# Sheet1.net
KiCad netlist of a schematic drawn in Altium Designer
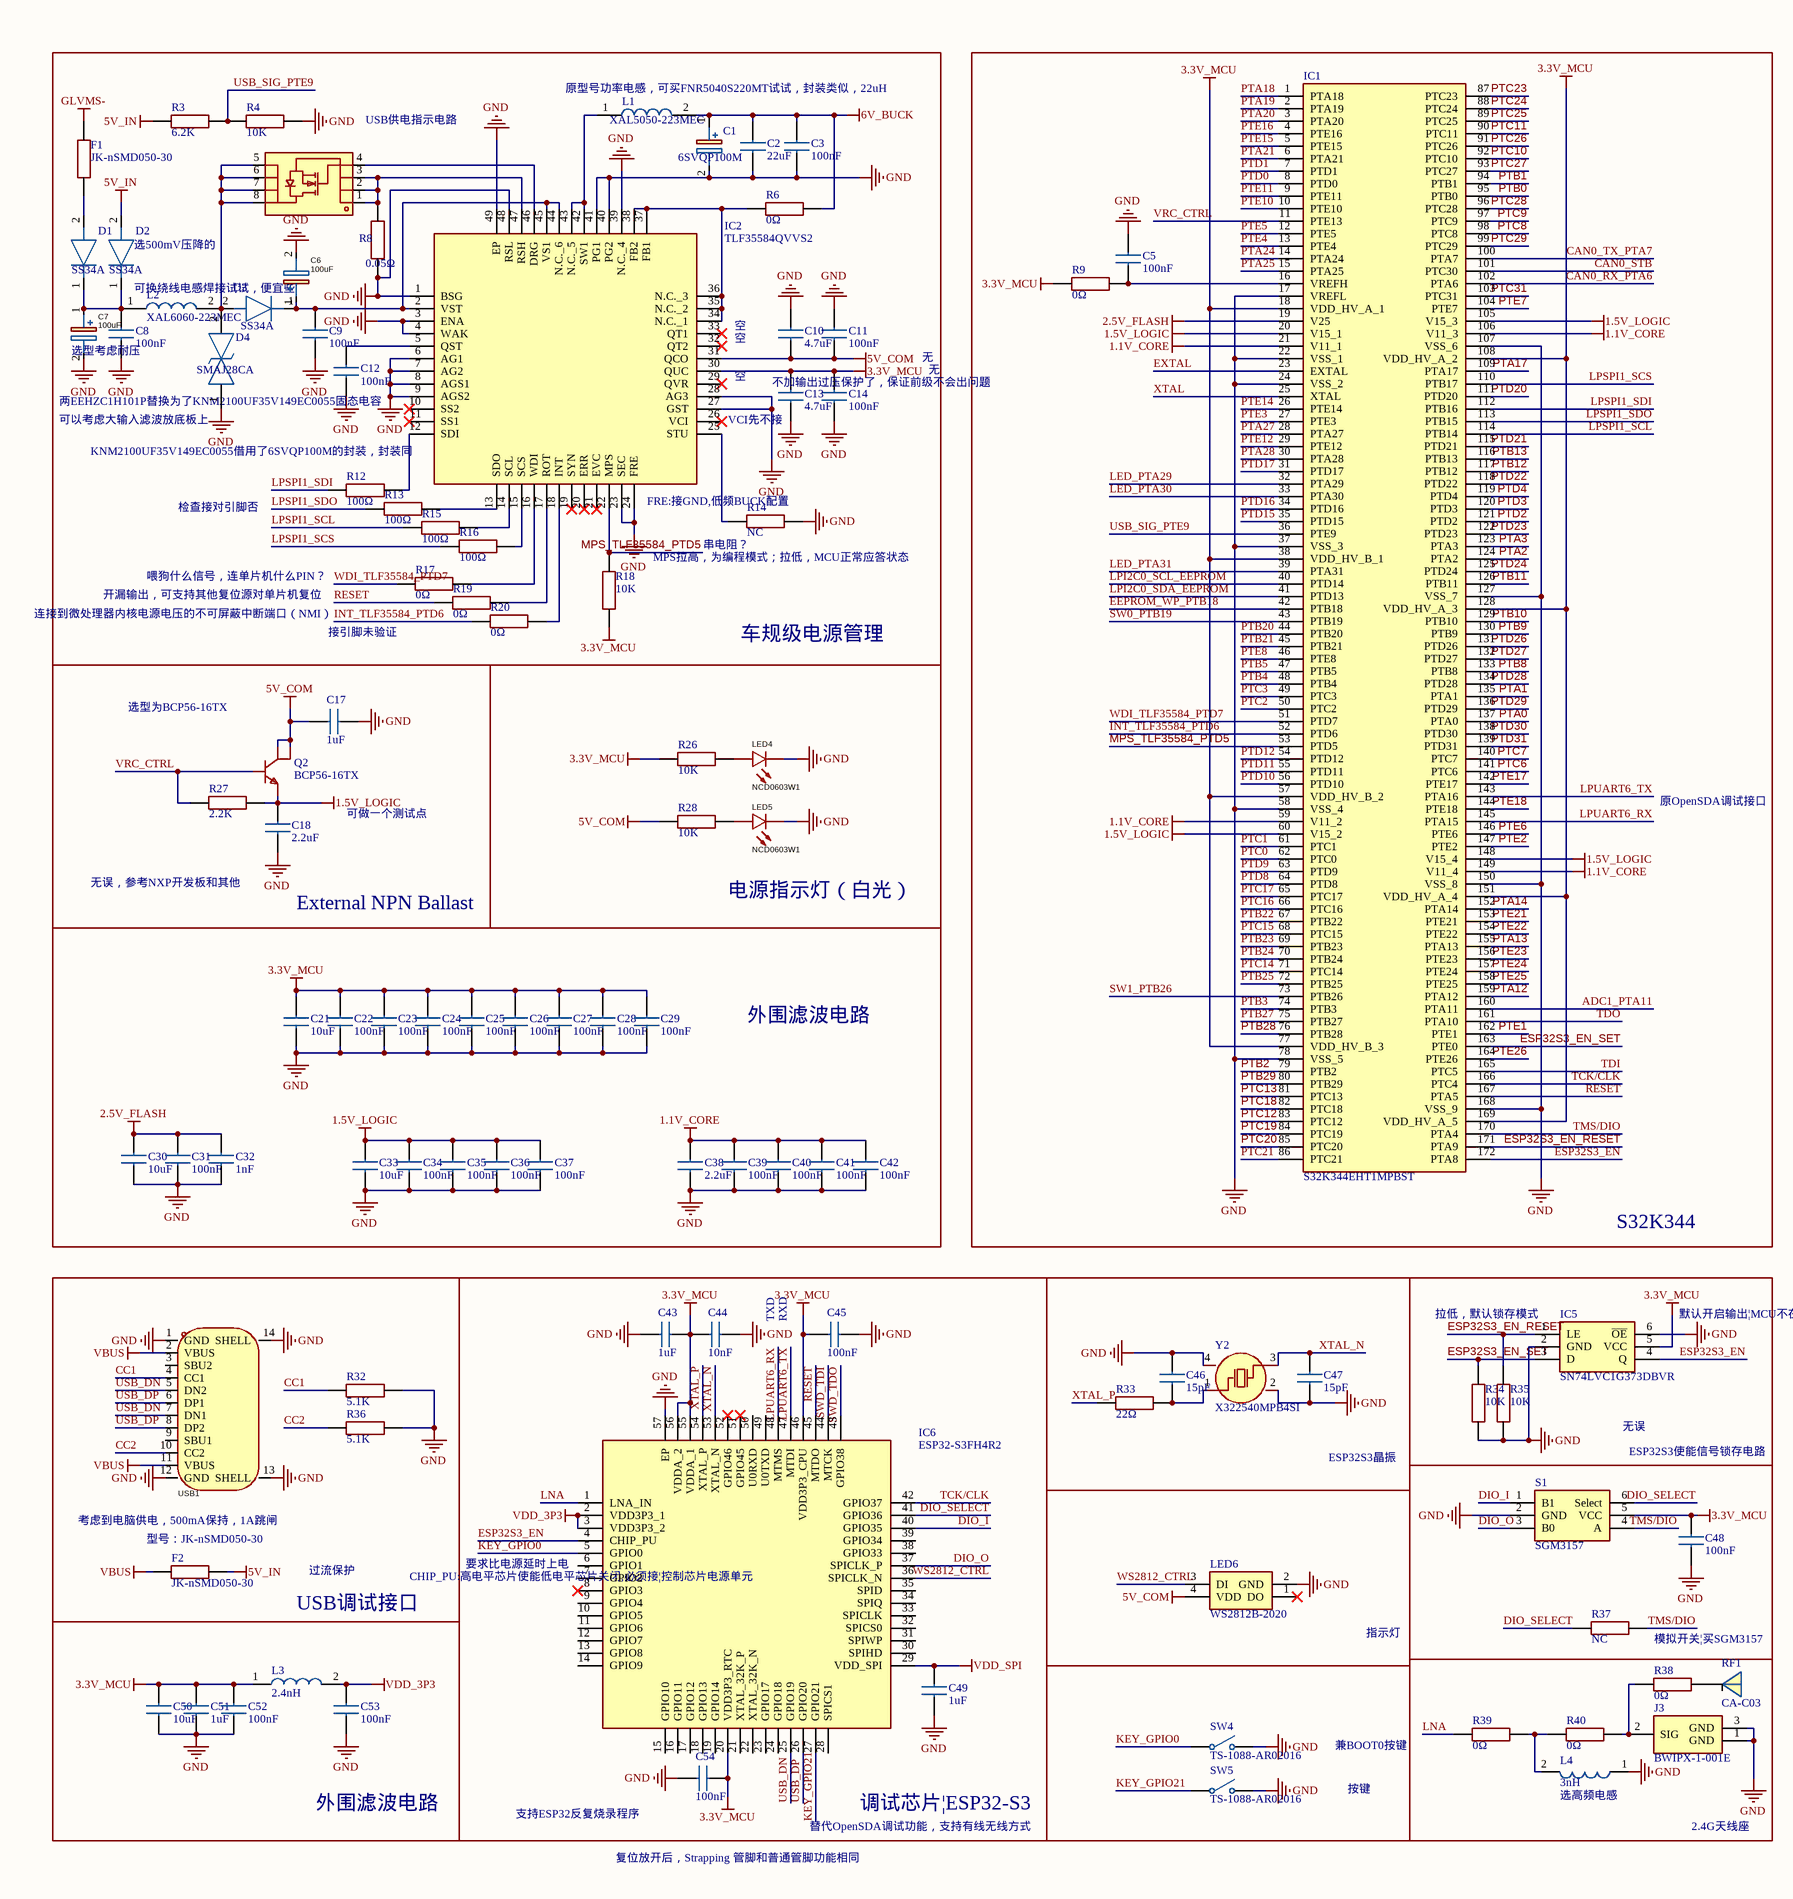
[diagram p0: Sheet1.SchDoc, left]
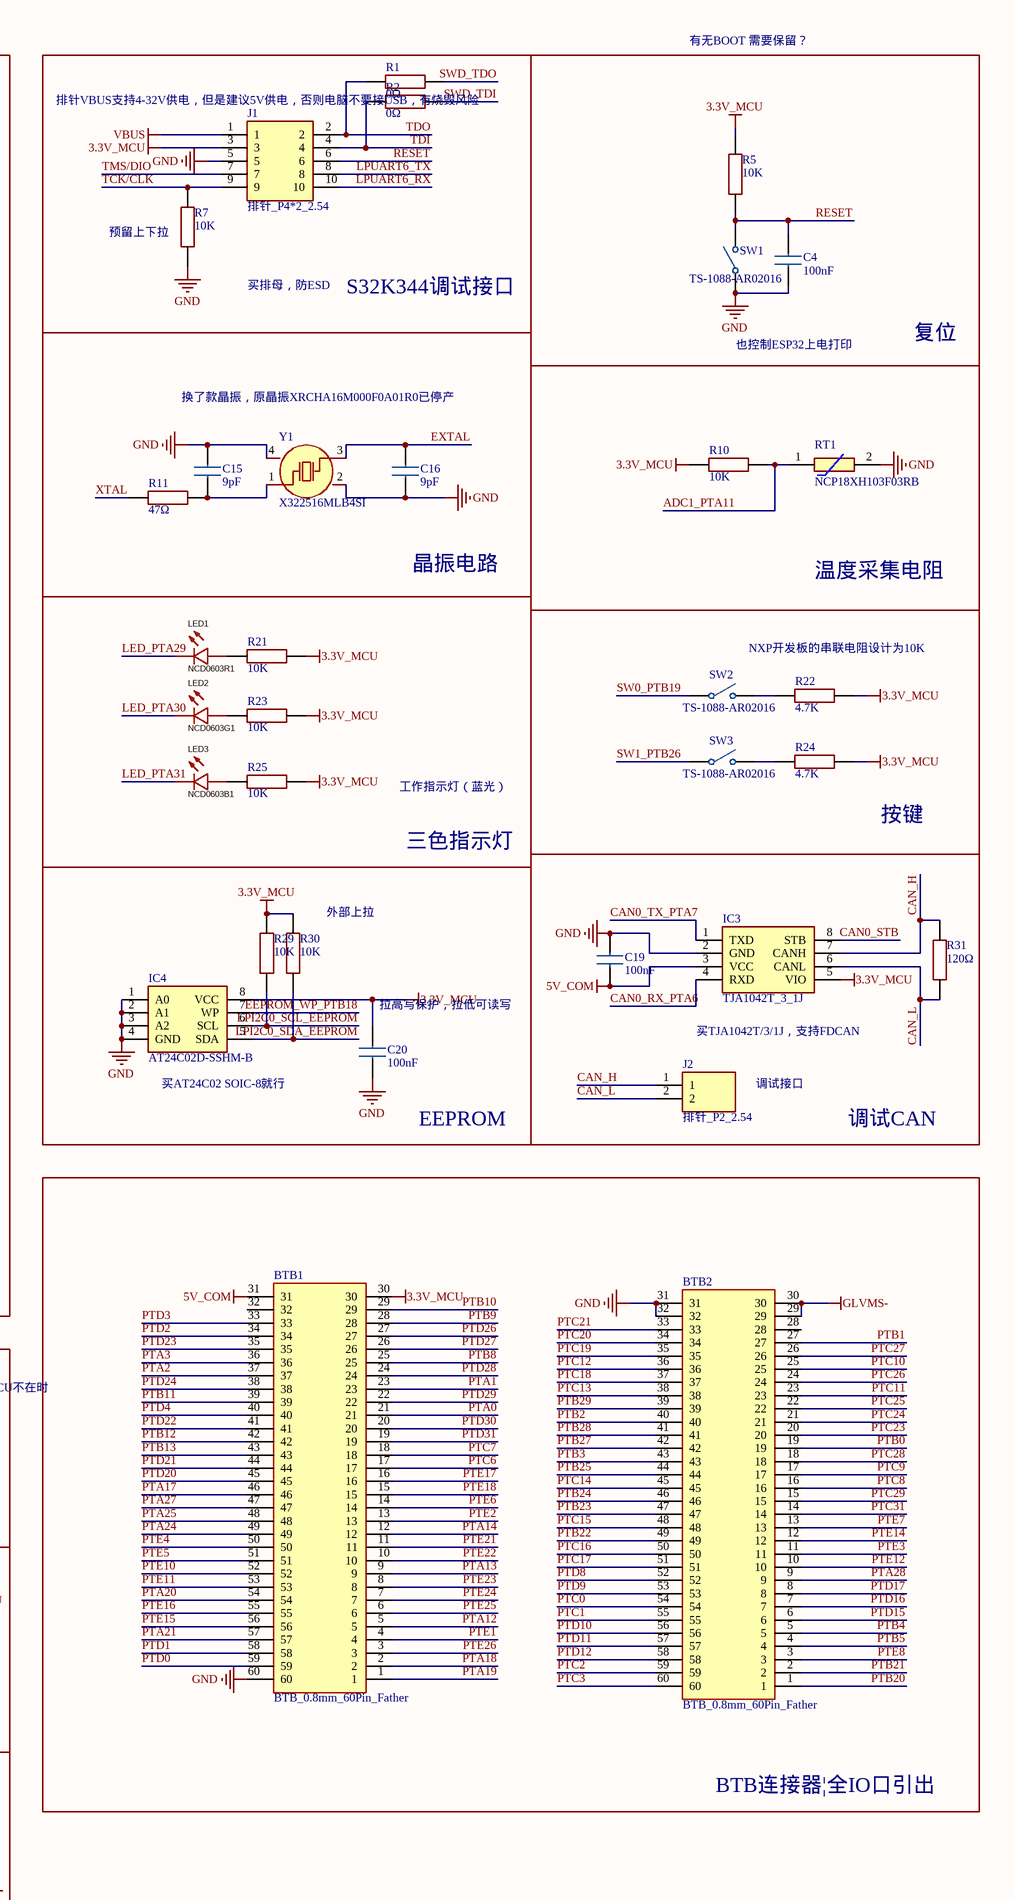
[diagram p1: Sheet1.SchDoc, right]

(export (version "E")
  (design (tool "Eeschema 10.0.6"))
  (components
    (comp (ref "BTB1")
      (value "BTB_0.8mm_60Pin_Father")
      (footprint "BTB_0.8mm_60PIN_F")
      (libsource (lib "Connector") (part "BTB_0.8mm_60Pin_Father"))
    )
    (comp (ref "BTB2")
      (value "BTB_0.8mm_60Pin_Father")
      (footprint "BTB_0.8mm_60PIN_F")
      (libsource (lib "Connector") (part "BTB_0.8mm_60Pin_Father"))
    )
    (comp (ref "C1")
      (value "6SVQP100M")
      (footprint "16SVF180M")
      (description "Capacitor Polarised")
      (fields (field (name "MOUSER PART NUMBER") "667-6SVQP100M"))
      (libsource (lib "Resistor^Capacitor^Inductor") (part "6SVQP100M"))
    )
    (comp (ref "C2")
      (value "22uF")
      (footprint "CAPC1608X90N")
      (description "Capacitor CC0603KRX7R9BB104")
      (fields
        (field (name "MANUFACTURER_PART_NUMBER") "CC0603KRX7R9BB104")
        (field (name "MOUSER PART NUMBER") "603-CC603KRX7R9BB104")
      )
      (libsource (lib "Resistor^Capacitor^Inductor") (part "C0603"))
    )
    (comp (ref "C3")
      (value "100nF")
      (footprint "CAPC1608X90N")
      (description "Capacitor CC0603KRX7R9BB104")
      (fields
        (field (name "MANUFACTURER_PART_NUMBER") "CC0603KRX7R9BB104")
        (field (name "MOUSER PART NUMBER") "603-CC603KRX7R9BB104")
      )
      (libsource (lib "Resistor^Capacitor^Inductor") (part "C0603"))
    )
    (comp (ref "C4")
      (value "100nF")
      (footprint "CAPC1608X90N")
      (description "Capacitor CC0603KRX7R9BB104")
      (fields
        (field (name "MANUFACTURER_PART_NUMBER") "CC0603KRX7R9BB104")
        (field (name "MOUSER PART NUMBER") "603-CC603KRX7R9BB104")
      )
      (libsource (lib "Resistor^Capacitor^Inductor") (part "C0603"))
    )
    (comp (ref "C5")
      (value "100nF")
      (footprint "CAPC1608X90N")
      (description "Capacitor CC0603KRX7R9BB104")
      (fields
        (field (name "MANUFACTURER_PART_NUMBER") "CC0603KRX7R9BB104")
        (field (name "MOUSER PART NUMBER") "603-CC603KRX7R9BB104")
      )
      (libsource (lib "Resistor^Capacitor^Inductor") (part "C0603"))
    )
    (comp (ref "C6")
      (value "100uF")
      (footprint "16SVF180M")
      (fields
        (field (name "MANUFACTURER") "KNSCHA(科尼盛)")
        (field (name "MANUFACTURER PART") "KNM2100UF35V149EC0055")
        (field (name "TOLERANCE") "±20%")
      )
      (libsource (lib "Resistor^Capacitor^Inductor") (part "KNM2100UF35V149EC0055"))
    )
    (comp (ref "C7")
      (value "100uF")
      (footprint "16SVF180M")
      (fields
        (field (name "MANUFACTURER") "KNSCHA(科尼盛)")
        (field (name "MANUFACTURER PART") "KNM2100UF35V149EC0055")
        (field (name "TOLERANCE") "±20%")
      )
      (libsource (lib "") (part "KNM2100UF35V149EC0055_1"))
    )
    (comp (ref "C8")
      (value "100nF")
      (footprint "CAPC1608X90N")
      (description "Capacitor CC0603KRX7R9BB104")
      (fields
        (field (name "MANUFACTURER_PART_NUMBER") "CC0603KRX7R9BB104")
        (field (name "MOUSER PART NUMBER") "603-CC603KRX7R9BB104")
      )
      (libsource (lib "Resistor^Capacitor^Inductor") (part "C0603"))
    )
    (comp (ref "C9")
      (value "100nF")
      (footprint "CAPC1608X90N")
      (description "Capacitor CC0603KRX7R9BB104")
      (fields
        (field (name "MANUFACTURER_PART_NUMBER") "CC0603KRX7R9BB104")
        (field (name "MOUSER PART NUMBER") "603-CC603KRX7R9BB104")
      )
      (libsource (lib "Resistor^Capacitor^Inductor") (part "C0603"))
    )
    (comp (ref "C10")
      (value "4.7uF")
      (footprint "CAPC1608X90N")
      (description "Capacitor CC0603KRX7R9BB104")
      (fields
        (field (name "MANUFACTURER_PART_NUMBER") "CC0603KRX7R9BB104")
        (field (name "MOUSER PART NUMBER") "603-CC603KRX7R9BB104")
      )
      (libsource (lib "Resistor^Capacitor^Inductor") (part "C0603"))
    )
    (comp (ref "C11")
      (value "100nF")
      (footprint "CAPC1608X90N")
      (description "Capacitor CC0603KRX7R9BB104")
      (fields
        (field (name "MANUFACTURER_PART_NUMBER") "CC0603KRX7R9BB104")
        (field (name "MOUSER PART NUMBER") "603-CC603KRX7R9BB104")
      )
      (libsource (lib "Resistor^Capacitor^Inductor") (part "C0603"))
    )
    (comp (ref "C12")
      (value "100nF")
      (footprint "CAPC1608X90N")
      (description "Capacitor CC0603KRX7R9BB104")
      (fields
        (field (name "MANUFACTURER_PART_NUMBER") "CC0603KRX7R9BB104")
        (field (name "MOUSER PART NUMBER") "603-CC603KRX7R9BB104")
      )
      (libsource (lib "Resistor^Capacitor^Inductor") (part "C0603"))
    )
    (comp (ref "C13")
      (value "4.7uF")
      (footprint "CAPC1608X90N")
      (description "Capacitor CC0603KRX7R9BB104")
      (fields
        (field (name "MANUFACTURER_PART_NUMBER") "CC0603KRX7R9BB104")
        (field (name "MOUSER PART NUMBER") "603-CC603KRX7R9BB104")
      )
      (libsource (lib "Resistor^Capacitor^Inductor") (part "C0603"))
    )
    (comp (ref "C14")
      (value "100nF")
      (footprint "CAPC1608X90N")
      (description "Capacitor CC0603KRX7R9BB104")
      (fields
        (field (name "MANUFACTURER_PART_NUMBER") "CC0603KRX7R9BB104")
        (field (name "MOUSER PART NUMBER") "603-CC603KRX7R9BB104")
      )
      (libsource (lib "Resistor^Capacitor^Inductor") (part "C0603"))
    )
    (comp (ref "C15")
      (value "9pF")
      (footprint "CAPC1608X90N")
      (description "Capacitor CC0603KRX7R9BB104")
      (fields
        (field (name "MANUFACTURER_PART_NUMBER") "CC0603KRX7R9BB104")
        (field (name "MOUSER PART NUMBER") "603-CC603KRX7R9BB104")
      )
      (libsource (lib "Resistor^Capacitor^Inductor") (part "C0603"))
    )
    (comp (ref "C16")
      (value "9pF")
      (footprint "CAPC1608X90N")
      (description "Capacitor CC0603KRX7R9BB104")
      (fields
        (field (name "MANUFACTURER_PART_NUMBER") "CC0603KRX7R9BB104")
        (field (name "MOUSER PART NUMBER") "603-CC603KRX7R9BB104")
      )
      (libsource (lib "Resistor^Capacitor^Inductor") (part "C0603"))
    )
    (comp (ref "C17")
      (value "1uF")
      (footprint "CAPC1608X90N")
      (description "Capacitor CC0603KRX7R9BB104")
      (fields
        (field (name "MANUFACTURER_PART_NUMBER") "CC0603KRX7R9BB104")
        (field (name "MOUSER PART NUMBER") "603-CC603KRX7R9BB104")
      )
      (libsource (lib "Resistor^Capacitor^Inductor") (part "C0603"))
    )
    (comp (ref "C18")
      (value "2.2uF")
      (footprint "CAPC1608X90N")
      (description "Capacitor CC0603KRX7R9BB104")
      (fields
        (field (name "MANUFACTURER_PART_NUMBER") "CC0603KRX7R9BB104")
        (field (name "MOUSER PART NUMBER") "603-CC603KRX7R9BB104")
      )
      (libsource (lib "Resistor^Capacitor^Inductor") (part "C0603"))
    )
    (comp (ref "C19")
      (value "100nF")
      (footprint "CAPC1608X90N")
      (description "Capacitor CC0603KRX7R9BB104")
      (fields
        (field (name "MANUFACTURER_PART_NUMBER") "CC0603KRX7R9BB104")
        (field (name "MOUSER PART NUMBER") "603-CC603KRX7R9BB104")
      )
      (libsource (lib "Resistor^Capacitor^Inductor") (part "C0603"))
    )
    (comp (ref "C20")
      (value "100nF")
      (footprint "CAPC1608X90N")
      (description "Capacitor CC0603KRX7R9BB104")
      (fields
        (field (name "MANUFACTURER_PART_NUMBER") "CC0603KRX7R9BB104")
        (field (name "MOUSER PART NUMBER") "603-CC603KRX7R9BB104")
      )
      (libsource (lib "Resistor^Capacitor^Inductor") (part "C0603"))
    )
    (comp (ref "C21")
      (value "10uF")
      (footprint "CAPC1608X90N")
      (description "Capacitor CC0603KRX7R9BB104")
      (fields
        (field (name "MANUFACTURER_PART_NUMBER") "CC0603KRX7R9BB104")
        (field (name "MOUSER PART NUMBER") "603-CC603KRX7R9BB104")
      )
      (libsource (lib "Resistor^Capacitor^Inductor") (part "C0603"))
    )
    (comp (ref "C22")
      (value "100nF")
      (footprint "CAPC1608X90N")
      (description "Capacitor CC0603KRX7R9BB104")
      (fields
        (field (name "MANUFACTURER_PART_NUMBER") "CC0603KRX7R9BB104")
        (field (name "MOUSER PART NUMBER") "603-CC603KRX7R9BB104")
      )
      (libsource (lib "Resistor^Capacitor^Inductor") (part "C0603"))
    )
    (comp (ref "C23")
      (value "100nF")
      (footprint "CAPC1608X90N")
      (description "Capacitor CC0603KRX7R9BB104")
      (fields
        (field (name "MANUFACTURER_PART_NUMBER") "CC0603KRX7R9BB104")
        (field (name "MOUSER PART NUMBER") "603-CC603KRX7R9BB104")
      )
      (libsource (lib "Resistor^Capacitor^Inductor") (part "C0603"))
    )
    (comp (ref "C24")
      (value "100nF")
      (footprint "CAPC1608X90N")
      (description "Capacitor CC0603KRX7R9BB104")
      (fields
        (field (name "MANUFACTURER_PART_NUMBER") "CC0603KRX7R9BB104")
        (field (name "MOUSER PART NUMBER") "603-CC603KRX7R9BB104")
      )
      (libsource (lib "Resistor^Capacitor^Inductor") (part "C0603"))
    )
    (comp (ref "C25")
      (value "100nF")
      (footprint "CAPC1608X90N")
      (description "Capacitor CC0603KRX7R9BB104")
      (fields
        (field (name "MANUFACTURER_PART_NUMBER") "CC0603KRX7R9BB104")
        (field (name "MOUSER PART NUMBER") "603-CC603KRX7R9BB104")
      )
      (libsource (lib "Resistor^Capacitor^Inductor") (part "C0603"))
    )
    (comp (ref "C26")
      (value "100nF")
      (footprint "CAPC1608X90N")
      (description "Capacitor CC0603KRX7R9BB104")
      (fields
        (field (name "MANUFACTURER_PART_NUMBER") "CC0603KRX7R9BB104")
        (field (name "MOUSER PART NUMBER") "603-CC603KRX7R9BB104")
      )
      (libsource (lib "Resistor^Capacitor^Inductor") (part "C0603"))
    )
    (comp (ref "C27")
      (value "100nF")
      (footprint "CAPC1608X90N")
      (description "Capacitor CC0603KRX7R9BB104")
      (fields
        (field (name "MANUFACTURER_PART_NUMBER") "CC0603KRX7R9BB104")
        (field (name "MOUSER PART NUMBER") "603-CC603KRX7R9BB104")
      )
      (libsource (lib "Resistor^Capacitor^Inductor") (part "C0603"))
    )
    (comp (ref "C28")
      (value "100nF")
      (footprint "CAPC1608X90N")
      (description "Capacitor CC0603KRX7R9BB104")
      (fields
        (field (name "MANUFACTURER_PART_NUMBER") "CC0603KRX7R9BB104")
        (field (name "MOUSER PART NUMBER") "603-CC603KRX7R9BB104")
      )
      (libsource (lib "Resistor^Capacitor^Inductor") (part "C0603"))
    )
    (comp (ref "C29")
      (value "100nF")
      (footprint "CAPC1608X90N")
      (description "Capacitor CC0603KRX7R9BB104")
      (fields
        (field (name "MANUFACTURER_PART_NUMBER") "CC0603KRX7R9BB104")
        (field (name "MOUSER PART NUMBER") "603-CC603KRX7R9BB104")
      )
      (libsource (lib "Resistor^Capacitor^Inductor") (part "C0603"))
    )
    (comp (ref "C30")
      (value "10uF")
      (footprint "CAPC1608X90N")
      (description "Capacitor CC0603KRX7R9BB104")
      (fields
        (field (name "MANUFACTURER_PART_NUMBER") "CC0603KRX7R9BB104")
        (field (name "MOUSER PART NUMBER") "603-CC603KRX7R9BB104")
      )
      (libsource (lib "Resistor^Capacitor^Inductor") (part "C0603"))
    )
    (comp (ref "C31")
      (value "100nF")
      (footprint "CAPC1608X90N")
      (description "Capacitor CC0603KRX7R9BB104")
      (fields
        (field (name "MANUFACTURER_PART_NUMBER") "CC0603KRX7R9BB104")
        (field (name "MOUSER PART NUMBER") "603-CC603KRX7R9BB104")
      )
      (libsource (lib "Resistor^Capacitor^Inductor") (part "C0603"))
    )
    (comp (ref "C32")
      (value "1nF")
      (footprint "CAPC1608X90N")
      (description "Capacitor CC0603KRX7R9BB104")
      (fields
        (field (name "MANUFACTURER_PART_NUMBER") "CC0603KRX7R9BB104")
        (field (name "MOUSER PART NUMBER") "603-CC603KRX7R9BB104")
      )
      (libsource (lib "Resistor^Capacitor^Inductor") (part "C0603"))
    )
    (comp (ref "C33")
      (value "10uF")
      (footprint "CAPC1608X90N")
      (description "Capacitor CC0603KRX7R9BB104")
      (fields
        (field (name "MANUFACTURER_PART_NUMBER") "CC0603KRX7R9BB104")
        (field (name "MOUSER PART NUMBER") "603-CC603KRX7R9BB104")
      )
      (libsource (lib "Resistor^Capacitor^Inductor") (part "C0603"))
    )
    (comp (ref "C34")
      (value "100nF")
      (footprint "CAPC1608X90N")
      (description "Capacitor CC0603KRX7R9BB104")
      (fields
        (field (name "MANUFACTURER_PART_NUMBER") "CC0603KRX7R9BB104")
        (field (name "MOUSER PART NUMBER") "603-CC603KRX7R9BB104")
      )
      (libsource (lib "Resistor^Capacitor^Inductor") (part "C0603"))
    )
    (comp (ref "C35")
      (value "100nF")
      (footprint "CAPC1608X90N")
      (description "Capacitor CC0603KRX7R9BB104")
      (fields
        (field (name "MANUFACTURER_PART_NUMBER") "CC0603KRX7R9BB104")
        (field (name "MOUSER PART NUMBER") "603-CC603KRX7R9BB104")
      )
      (libsource (lib "Resistor^Capacitor^Inductor") (part "C0603"))
    )
    (comp (ref "C36")
      (value "100nF")
      (footprint "CAPC1608X90N")
      (description "Capacitor CC0603KRX7R9BB104")
      (fields
        (field (name "MANUFACTURER_PART_NUMBER") "CC0603KRX7R9BB104")
        (field (name "MOUSER PART NUMBER") "603-CC603KRX7R9BB104")
      )
      (libsource (lib "Resistor^Capacitor^Inductor") (part "C0603"))
    )
    (comp (ref "C37")
      (value "100nF")
      (footprint "CAPC1608X90N")
      (description "Capacitor CC0603KRX7R9BB104")
      (fields
        (field (name "MANUFACTURER_PART_NUMBER") "CC0603KRX7R9BB104")
        (field (name "MOUSER PART NUMBER") "603-CC603KRX7R9BB104")
      )
      (libsource (lib "Resistor^Capacitor^Inductor") (part "C0603"))
    )
    (comp (ref "C38")
      (value "2.2uF")
      (footprint "CAPC1608X90N")
      (description "Capacitor CC0603KRX7R9BB104")
      (fields
        (field (name "MANUFACTURER_PART_NUMBER") "CC0603KRX7R9BB104")
        (field (name "MOUSER PART NUMBER") "603-CC603KRX7R9BB104")
      )
      (libsource (lib "Resistor^Capacitor^Inductor") (part "C0603"))
    )
    (comp (ref "C39")
      (value "100nF")
      (footprint "CAPC1608X90N")
      (description "Capacitor CC0603KRX7R9BB104")
      (fields
        (field (name "MANUFACTURER_PART_NUMBER") "CC0603KRX7R9BB104")
        (field (name "MOUSER PART NUMBER") "603-CC603KRX7R9BB104")
      )
      (libsource (lib "Resistor^Capacitor^Inductor") (part "C0603"))
    )
    (comp (ref "C40")
      (value "100nF")
      (footprint "CAPC1608X90N")
      (description "Capacitor CC0603KRX7R9BB104")
      (fields
        (field (name "MANUFACTURER_PART_NUMBER") "CC0603KRX7R9BB104")
        (field (name "MOUSER PART NUMBER") "603-CC603KRX7R9BB104")
      )
      (libsource (lib "Resistor^Capacitor^Inductor") (part "C0603"))
    )
    (comp (ref "C41")
      (value "100nF")
      (footprint "CAPC1608X90N")
      (description "Capacitor CC0603KRX7R9BB104")
      (fields
        (field (name "MANUFACTURER_PART_NUMBER") "CC0603KRX7R9BB104")
        (field (name "MOUSER PART NUMBER") "603-CC603KRX7R9BB104")
      )
      (libsource (lib "Resistor^Capacitor^Inductor") (part "C0603"))
    )
    (comp (ref "C42")
      (value "100nF")
      (footprint "CAPC1608X90N")
      (description "Capacitor CC0603KRX7R9BB104")
      (fields
        (field (name "MANUFACTURER_PART_NUMBER") "CC0603KRX7R9BB104")
        (field (name "MOUSER PART NUMBER") "603-CC603KRX7R9BB104")
      )
      (libsource (lib "Resistor^Capacitor^Inductor") (part "C0603"))
    )
    (comp (ref "C43")
      (value "1uF")
      (footprint "CAPC1608X90N")
      (description "Capacitor CC0603KRX7R9BB104")
      (fields
        (field (name "MANUFACTURER_PART_NUMBER") "CC0603KRX7R9BB104")
        (field (name "MOUSER PART NUMBER") "603-CC603KRX7R9BB104")
      )
      (libsource (lib "Resistor^Capacitor^Inductor") (part "C0603"))
    )
    (comp (ref "C44")
      (value "10nF")
      (footprint "CAPC1608X90N")
      (description "Capacitor CC0603KRX7R9BB104")
      (fields
        (field (name "MANUFACTURER_PART_NUMBER") "CC0603KRX7R9BB104")
        (field (name "MOUSER PART NUMBER") "603-CC603KRX7R9BB104")
      )
      (libsource (lib "Resistor^Capacitor^Inductor") (part "C0603"))
    )
    (comp (ref "C45")
      (value "100nF")
      (footprint "CAPC1608X90N")
      (description "Capacitor CC0603KRX7R9BB104")
      (fields
        (field (name "MANUFACTURER_PART_NUMBER") "CC0603KRX7R9BB104")
        (field (name "MOUSER PART NUMBER") "603-CC603KRX7R9BB104")
      )
      (libsource (lib "Resistor^Capacitor^Inductor") (part "C0603"))
    )
    (comp (ref "C46")
      (value "15pF")
      (footprint "CAPC1608X90N")
      (description "Capacitor CC0603KRX7R9BB104")
      (fields
        (field (name "MANUFACTURER_PART_NUMBER") "CC0603KRX7R9BB104")
        (field (name "MOUSER PART NUMBER") "603-CC603KRX7R9BB104")
      )
      (libsource (lib "Resistor^Capacitor^Inductor") (part "C0603"))
    )
    (comp (ref "C47")
      (value "15pF")
      (footprint "CAPC1608X90N")
      (description "Capacitor CC0603KRX7R9BB104")
      (fields
        (field (name "MANUFACTURER_PART_NUMBER") "CC0603KRX7R9BB104")
        (field (name "MOUSER PART NUMBER") "603-CC603KRX7R9BB104")
      )
      (libsource (lib "Resistor^Capacitor^Inductor") (part "C0603"))
    )
    (comp (ref "C48")
      (value "100nF")
      (footprint "CAPC1608X90N")
      (description "Capacitor CC0603KRX7R9BB104")
      (fields
        (field (name "MANUFACTURER_PART_NUMBER") "CC0603KRX7R9BB104")
        (field (name "MOUSER PART NUMBER") "603-CC603KRX7R9BB104")
      )
      (libsource (lib "Resistor^Capacitor^Inductor") (part "C0603"))
    )
    (comp (ref "C49")
      (value "1uF")
      (footprint "CAPC1608X90N")
      (description "Capacitor CC0603KRX7R9BB104")
      (fields
        (field (name "MANUFACTURER_PART_NUMBER") "CC0603KRX7R9BB104")
        (field (name "MOUSER PART NUMBER") "603-CC603KRX7R9BB104")
      )
      (libsource (lib "Resistor^Capacitor^Inductor") (part "C0603"))
    )
    (comp (ref "C50")
      (value "10uF")
      (footprint "CAPC1608X90N")
      (description "Capacitor CC0603KRX7R9BB104")
      (fields
        (field (name "MANUFACTURER_PART_NUMBER") "CC0603KRX7R9BB104")
        (field (name "MOUSER PART NUMBER") "603-CC603KRX7R9BB104")
      )
      (libsource (lib "Resistor^Capacitor^Inductor") (part "C0603"))
    )
    (comp (ref "C51")
      (value "1uF")
      (footprint "CAPC1608X90N")
      (description "Capacitor CC0603KRX7R9BB104")
      (fields
        (field (name "MANUFACTURER_PART_NUMBER") "CC0603KRX7R9BB104")
        (field (name "MOUSER PART NUMBER") "603-CC603KRX7R9BB104")
      )
      (libsource (lib "Resistor^Capacitor^Inductor") (part "C0603"))
    )
    (comp (ref "C52")
      (value "100nF")
      (footprint "CAPC1608X90N")
      (description "Capacitor CC0603KRX7R9BB104")
      (fields
        (field (name "MANUFACTURER_PART_NUMBER") "CC0603KRX7R9BB104")
        (field (name "MOUSER PART NUMBER") "603-CC603KRX7R9BB104")
      )
      (libsource (lib "Resistor^Capacitor^Inductor") (part "C0603"))
    )
    (comp (ref "C53")
      (value "100nF")
      (footprint "CAPC1608X90N")
      (description "Capacitor CC0603KRX7R9BB104")
      (fields
        (field (name "MANUFACTURER_PART_NUMBER") "CC0603KRX7R9BB104")
        (field (name "MOUSER PART NUMBER") "603-CC603KRX7R9BB104")
      )
      (libsource (lib "Resistor^Capacitor^Inductor") (part "C0603"))
    )
    (comp (ref "C54")
      (value "100nF")
      (footprint "CAPC1608X90N")
      (description "Capacitor CC0603KRX7R9BB104")
      (fields
        (field (name "MANUFACTURER_PART_NUMBER") "CC0603KRX7R9BB104")
        (field (name "MOUSER PART NUMBER") "603-CC603KRX7R9BB104")
      )
      (libsource (lib "Resistor^Capacitor^Inductor") (part "C0603"))
    )
    (comp (ref "D1")
      (value "SS34A")
      (footprint "DIOM5026X262N")
      (description "Diode")
      (libsource (lib "Diodes") (part "SS34A"))
    )
    (comp (ref "D2")
      (value "SS34A")
      (footprint "DIOM5026X262N")
      (description "Diode")
      (libsource (lib "Diodes") (part "SS34A"))
    )
    (comp (ref "D3")
      (value "SS34A")
      (footprint "DIOM5026X262N")
      (description "Diode")
      (libsource (lib "Diodes") (part "SS34A"))
    )
    (comp (ref "D4")
      (value "SMAJ28CA")
      (footprint "DIONM5226X262N")
      (description "TVS Diode (Bi-directional)")
      (fields (field (name "MOUSER PART NUMBER") "652-SMAJ28CA"))
      (libsource (lib "Diodes") (part "SMAJ28CA"))
    )
    (comp (ref "F1")
      (value "JK-nSMD050-30")
      (footprint "RESC3116X65N")
      (fields (field (name "MANUFACTURER_PART_NUMBER") "1206W4F1002T5E"))
      (libsource (lib "Resistor^Capacitor^Inductor") (part "R1206"))
    )
    (comp (ref "F2")
      (value "JK-nSMD050-30")
      (footprint "RESC3116X65N")
      (fields (field (name "MANUFACTURER_PART_NUMBER") "1206W4F1002T5E"))
      (libsource (lib "") (part "R1206_1"))
    )
    (comp (ref "IC1")
      (value "S32K344EHT1MPBST")
      (footprint "S32K344EHT1MPBST")
      (description "Integrated Circuit")
      (fields (field (name "MOUSER PART NUMBER") "771-S32K344EHT1MPBST"))
      (libsource (lib "MCU^MPU") (part "S32K344EHT1MPBST"))
    )
    (comp (ref "IC2")
      (value "TLF35584QVVS2")
      (footprint "QFN50P700X700X90-49N-D")
      (description "Integrated Circuit")
      (libsource (lib "LDO^DCDC^PMIC") (part "TLF35584QVVS2"))
    )
    (comp (ref "IC3")
      (value "TJA1042T_3_1J")
      (footprint "SOIC127P600X175-8N")
      (description "Integrated Circuit")
      (fields
        (field (name "MANUFACTURER_PART_NUMBER") "TJA1042T/3/1J")
        (field (name "MOUSER PART NUMBER") "771-TJA1042T/3/1J")
      )
      (libsource (lib "Transivers") (part "TJA1042T_3_1J"))
    )
    (comp (ref "IC4")
      (value "AT24C02D-SSHM-B")
      (footprint "SOIC127P600X175-8N")
      (description "Integrated Circuit")
      (fields (field (name "MOUSER PART NUMBER") "556-AT24C02D-SSHM-B"))
      (libsource (lib "Memory") (part "AT24C02D-SSHM-B"))
    )
    (comp (ref "IC5")
      (value "SN74LVC1G373DBVR")
      (footprint "SOT95P280X145-6N")
      (description "Integrated Circuit")
      (fields (field (name "MOUSER PART NUMBER") "595-SN74LVC1G373DBVR"))
      (libsource (lib "Logic") (part "SN74LVC1G373DBVR"))
    )
    (comp (ref "IC6")
      (value "ESP32-S3FH4R2")
      (footprint "QFN40P700X700X90-57N-D")
      (description "Integrated Circuit")
      (fields (field (name "MOUSER PART NUMBER") "356-ESP32-S3FH4R2"))
      (libsource (lib "MCU^MPU") (part "ESP32-S3FH4R2"))
    )
    (comp (ref "J1")
      (value "排针_P4*2_2.54")
      (footprint "ZXPZ25425PZZ")
      (description "Connector")
      (fields (field (name "MANUFACTURER_PART_NUMBER") "ZX-PZ2.54-2-5PZZ"))
      (libsource (lib "Connector") (part "排针_P4*2_2.54"))
    )
    (comp (ref "J2")
      (value "排针_P2_2.54")
      (footprint "HDRV2W66P0X254_1X2_508X250X880P")
      (description "Connector")
      (fields (field (name "MANUFACTURER_PART_NUMBER") "B-2100S02P-A110"))
      (libsource (lib "Connector") (part "排针_P2_2.54"))
    )
    (comp (ref "J3")
      (value "BWIPX-1-001E")
      (footprint "BWIPX1001E")
      (description "Connector")
      (libsource (lib "Connector") (part "BWIPX-1-001E"))
    )
    (comp (ref "L1")
      (value "XAL5050-223MEC")
      (footprint "XAL5030")
      (description "Inductor")
      (fields (field (name "MOUSER PART NUMBER") "994-XAL5050-223MEC"))
      (libsource (lib "Resistor^Capacitor^Inductor") (part "XAL5050-223MEC"))
    )
    (comp (ref "L2")
      (value "XAL6060-223MEC")
      (footprint "XAL6060822MEB")
      (description "Inductor")
      (fields (field (name "MOUSER PART NUMBER") "994-XAL6060-223MEC"))
      (libsource (lib "Resistor^Capacitor^Inductor") (part "XAL6060-223MEC"))
    )
    (comp (ref "L3")
      (value "2.4nH")
      (footprint "LQM18FN100M00D")
      (description "Inductor")
      (fields
        (field (name "MANUFACTURER_PART_NUMBER") "LQM18FN100M00D")
        (field (name "MOUSER PART NUMBER") "81-LQM18FN100M00D")
      )
      (libsource (lib "Resistor^Capacitor^Inductor") (part "L0603"))
    )
    (comp (ref "L4")
      (value "3nH")
      (footprint "LQM18FN100M00D")
      (description "Inductor")
      (fields
        (field (name "MANUFACTURER_PART_NUMBER") "LQM18FN100M00D")
        (field (name "MOUSER PART NUMBER") "81-LQM18FN100M00D")
      )
      (libsource (lib "Resistor^Capacitor^Inductor") (part "L0603"))
    )
    (comp (ref "LED1")
      (value "NCD0603R1")
      (footprint "LED0603-RD")
      (description "C84263")
      (fields (field (name "MANUFACTURER") "国星光电"))
      (libsource (lib "Diodes") (part "NCD0603R1"))
    )
    (comp (ref "LED2")
      (value "NCD0603G1")
      (footprint "LED0603-RD_1")
      (fields (field (name "MANUFACTURER") "国星光电"))
      (libsource (lib "Diodes") (part "NCD0603G1"))
    )
    (comp (ref "LED3")
      (value "NCD0603B1")
      (footprint "LED0603-RD")
      (fields (field (name "MANUFACTURER") "国星光电"))
      (libsource (lib "Diodes") (part "NCD0603B1"))
    )
    (comp (ref "LED4")
      (value "NCD0603W1")
      (footprint "LED0603-RD")
      (fields (field (name "MANUFACTURER") "国星光电"))
      (libsource (lib "Diodes") (part "NCD0603W1"))
    )
    (comp (ref "LED5")
      (value "NCD0603W1")
      (footprint "LED0603-RD")
      (fields (field (name "MANUFACTURER") "国星光电"))
      (libsource (lib "Diodes") (part "NCD0603W1"))
    )
    (comp (ref "LED6")
      (value "WS2812B-2020")
      (footprint "WS2812B2020")
      (description "LED (Multiple)")
      (libsource (lib "Diodes") (part "WS2812B-2020"))
    )
    (comp (ref "Q1")
      (value "IPZ40N04S5L-7R4")
      (footprint "IPZ40N04S5L7R4ATMA1")
      (fields (field (name "MANUFACTURER") "Infineon(英飞凌)"))
      (libsource (lib "Triode^MOS^Transistor") (part "IPZ40N04S5L-7R4"))
    )
    (comp (ref "Q2")
      (value "BCP56-16TX")
      (footprint "SOT230P700X180-4N")
      (description "Transistor")
      (fields
        (field (name "MANUFACTURER_PART_NUMBER") "BCP56-16,115")
        (field (name "MOUSER PART NUMBER") "771-BCP56-16-T/R")
      )
      (libsource (lib "Triode^MOS^Transistor") (part "BCP56-16TX"))
    )
    (comp (ref "R1")
      (value "0Ω")
      (footprint "RESC1608X55N")
      (description "Resistor 0603WAF1002T5E")
      (fields (field (name "MANUFACTURER_PART_NUMBER") "0603WAF1002T5E"))
      (libsource (lib "Resistor^Capacitor^Inductor") (part "R0603"))
    )
    (comp (ref "R2")
      (value "0Ω")
      (footprint "RESC1608X55N")
      (description "Resistor 0603WAF1002T5E")
      (fields (field (name "MANUFACTURER_PART_NUMBER") "0603WAF1002T5E"))
      (libsource (lib "Resistor^Capacitor^Inductor") (part "R0603"))
    )
    (comp (ref "R3")
      (value "6.2K")
      (footprint "RESC1608X55N")
      (description "Resistor 0603WAF1002T5E")
      (fields (field (name "MANUFACTURER_PART_NUMBER") "0603WAF1002T5E"))
      (libsource (lib "Resistor^Capacitor^Inductor") (part "R0603"))
    )
    (comp (ref "R4")
      (value "10K")
      (footprint "RESC1608X55N")
      (description "Resistor 0603WAF1002T5E")
      (fields (field (name "MANUFACTURER_PART_NUMBER") "0603WAF1002T5E"))
      (libsource (lib "Resistor^Capacitor^Inductor") (part "R0603"))
    )
    (comp (ref "R5")
      (value "10K")
      (footprint "RESC1608X55N")
      (description "Resistor 0603WAF1002T5E")
      (fields (field (name "MANUFACTURER_PART_NUMBER") "0603WAF1002T5E"))
      (libsource (lib "") (part "R0603_1"))
    )
    (comp (ref "R6")
      (value "0Ω")
      (footprint "RESC1608X55N")
      (description "Resistor 0603WAF1002T5E")
      (fields (field (name "MANUFACTURER_PART_NUMBER") "0603WAF1002T5E"))
      (libsource (lib "Resistor^Capacitor^Inductor") (part "R0603"))
    )
    (comp (ref "R7")
      (value "10K")
      (footprint "RESC1608X55N")
      (description "Resistor 0603WAF1002T5E")
      (fields (field (name "MANUFACTURER_PART_NUMBER") "0603WAF1002T5E"))
      (libsource (lib "") (part "R0603_1"))
    )
    (comp (ref "R8")
      (value "0.05Ω")
      (footprint "RESC3116X65N")
      (description "Resistor 1206W4F1002T5E")
      (fields (field (name "MANUFACTURER_PART_NUMBER") "1206W4F1002T5E"))
      (libsource (lib "Resistor^Capacitor^Inductor") (part "R1206"))
    )
    (comp (ref "R9")
      (value "0Ω")
      (footprint "RESC1608X55N")
      (description "Resistor 0603WAF1002T5E")
      (fields (field (name "MANUFACTURER_PART_NUMBER") "0603WAF1002T5E"))
      (libsource (lib "Resistor^Capacitor^Inductor") (part "R0603"))
    )
    (comp (ref "R10")
      (value "10K")
      (footprint "RESC1608X55N")
      (description "Resistor 0603WAF1002T5E")
      (fields (field (name "MANUFACTURER_PART_NUMBER") "0603WAF1002T5E"))
      (libsource (lib "Resistor^Capacitor^Inductor") (part "R0603"))
    )
    (comp (ref "R11")
      (value "47Ω")
      (footprint "RESC1608X55N")
      (description "Resistor 0603WAF1002T5E")
      (fields (field (name "MANUFACTURER_PART_NUMBER") "0603WAF1002T5E"))
      (libsource (lib "Resistor^Capacitor^Inductor") (part "R0603"))
    )
    (comp (ref "R12")
      (value "100Ω")
      (footprint "RESC1608X55N")
      (description "Resistor 0603WAF1002T5E")
      (fields (field (name "MANUFACTURER_PART_NUMBER") "0603WAF1002T5E"))
      (libsource (lib "Resistor^Capacitor^Inductor") (part "R0603"))
    )
    (comp (ref "R13")
      (value "100Ω")
      (footprint "RESC1608X55N")
      (description "Resistor 0603WAF1002T5E")
      (fields (field (name "MANUFACTURER_PART_NUMBER") "0603WAF1002T5E"))
      (libsource (lib "Resistor^Capacitor^Inductor") (part "R0603"))
    )
    (comp (ref "R14")
      (value "NC")
      (footprint "RESC1608X55N")
      (description "Resistor 0603WAF1002T5E")
      (fields (field (name "MANUFACTURER_PART_NUMBER") "0603WAF1002T5E"))
      (libsource (lib "Resistor^Capacitor^Inductor") (part "R0603"))
    )
    (comp (ref "R15")
      (value "100Ω")
      (footprint "RESC1608X55N")
      (description "Resistor 0603WAF1002T5E")
      (fields (field (name "MANUFACTURER_PART_NUMBER") "0603WAF1002T5E"))
      (libsource (lib "Resistor^Capacitor^Inductor") (part "R0603"))
    )
    (comp (ref "R16")
      (value "100Ω")
      (footprint "RESC1608X55N")
      (description "Resistor 0603WAF1002T5E")
      (fields (field (name "MANUFACTURER_PART_NUMBER") "0603WAF1002T5E"))
      (libsource (lib "Resistor^Capacitor^Inductor") (part "R0603"))
    )
    (comp (ref "R17")
      (value "0Ω")
      (footprint "RESC1608X55N")
      (description "Resistor 0603WAF1002T5E")
      (fields (field (name "MANUFACTURER_PART_NUMBER") "0603WAF1002T5E"))
      (libsource (lib "Resistor^Capacitor^Inductor") (part "R0603"))
    )
    (comp (ref "R18")
      (value "10K")
      (footprint "RESC1608X55N")
      (description "Resistor 0603WAF1002T5E")
      (fields (field (name "MANUFACTURER_PART_NUMBER") "0603WAF1002T5E"))
      (libsource (lib "") (part "R0603_1"))
    )
    (comp (ref "R19")
      (value "0Ω")
      (footprint "RESC1608X55N")
      (description "Resistor 0603WAF1002T5E")
      (fields (field (name "MANUFACTURER_PART_NUMBER") "0603WAF1002T5E"))
      (libsource (lib "Resistor^Capacitor^Inductor") (part "R0603"))
    )
    (comp (ref "R20")
      (value "0Ω")
      (footprint "RESC1608X55N")
      (description "Resistor 0603WAF1002T5E")
      (fields (field (name "MANUFACTURER_PART_NUMBER") "0603WAF1002T5E"))
      (libsource (lib "Resistor^Capacitor^Inductor") (part "R0603"))
    )
    (comp (ref "R21")
      (value "10K")
      (footprint "RESC1608X55N")
      (description "Resistor 0603WAF1002T5E")
      (fields (field (name "MANUFACTURER_PART_NUMBER") "0603WAF1002T5E"))
      (libsource (lib "Resistor^Capacitor^Inductor") (part "R0603"))
    )
    (comp (ref "R22")
      (value "4.7K")
      (footprint "RESC1608X55N")
      (description "Resistor 0603WAF1002T5E")
      (fields (field (name "MANUFACTURER_PART_NUMBER") "0603WAF1002T5E"))
      (libsource (lib "Resistor^Capacitor^Inductor") (part "R0603"))
    )
    (comp (ref "R23")
      (value "10K")
      (footprint "RESC1608X55N")
      (description "Resistor 0603WAF1002T5E")
      (fields (field (name "MANUFACTURER_PART_NUMBER") "0603WAF1002T5E"))
      (libsource (lib "Resistor^Capacitor^Inductor") (part "R0603"))
    )
    (comp (ref "R24")
      (value "4.7K")
      (footprint "RESC1608X55N")
      (description "Resistor 0603WAF1002T5E")
      (fields (field (name "MANUFACTURER_PART_NUMBER") "0603WAF1002T5E"))
      (libsource (lib "Resistor^Capacitor^Inductor") (part "R0603"))
    )
    (comp (ref "R25")
      (value "10K")
      (footprint "RESC1608X55N")
      (description "Resistor 0603WAF1002T5E")
      (fields (field (name "MANUFACTURER_PART_NUMBER") "0603WAF1002T5E"))
      (libsource (lib "Resistor^Capacitor^Inductor") (part "R0603"))
    )
    (comp (ref "R26")
      (value "10K")
      (footprint "RESC1608X55N")
      (description "Resistor 0603WAF1002T5E")
      (fields (field (name "MANUFACTURER_PART_NUMBER") "0603WAF1002T5E"))
      (libsource (lib "") (part "R0603_2"))
    )
    (comp (ref "R27")
      (value "2.2K")
      (footprint "RESC1608X55N")
      (description "Resistor 0603WAF1002T5E")
      (fields (field (name "MANUFACTURER_PART_NUMBER") "0603WAF1002T5E"))
      (libsource (lib "Resistor^Capacitor^Inductor") (part "R0603"))
    )
    (comp (ref "R28")
      (value "10K")
      (footprint "RESC1608X55N")
      (description "Resistor 0603WAF1002T5E")
      (fields (field (name "MANUFACTURER_PART_NUMBER") "0603WAF1002T5E"))
      (libsource (lib "") (part "R0603_2"))
    )
    (comp (ref "R29")
      (value "10K")
      (footprint "RESC1608X55N")
      (description "Resistor 0603WAF1002T5E")
      (fields (field (name "MANUFACTURER_PART_NUMBER") "0603WAF1002T5E"))
      (libsource (lib "") (part "R0603_1"))
    )
    (comp (ref "R30")
      (value "10K")
      (footprint "RESC1608X55N")
      (description "Resistor 0603WAF1002T5E")
      (fields (field (name "MANUFACTURER_PART_NUMBER") "0603WAF1002T5E"))
      (libsource (lib "") (part "R0603_1"))
    )
    (comp (ref "R31")
      (value "120Ω")
      (footprint "RESC1608X55N")
      (description "Resistor 0603WAF1002T5E")
      (fields (field (name "MANUFACTURER_PART_NUMBER") "0603WAF1002T5E"))
      (libsource (lib "") (part "R0603_1"))
    )
    (comp (ref "R32")
      (value "5.1K")
      (footprint "RESC1608X55N")
      (description "Resistor 0603WAF1002T5E")
      (fields (field (name "MANUFACTURER_PART_NUMBER") "0603WAF1002T5E"))
      (libsource (lib "Resistor^Capacitor^Inductor") (part "R0603"))
    )
    (comp (ref "R33")
      (value "22Ω")
      (footprint "RESC1608X55N")
      (description "Resistor 0603WAF1002T5E")
      (fields (field (name "MANUFACTURER_PART_NUMBER") "0603WAF1002T5E"))
      (libsource (lib "Resistor^Capacitor^Inductor") (part "R0603"))
    )
    (comp (ref "R34")
      (value "10K")
      (footprint "RESC1608X55N")
      (description "Resistor 0603WAF1002T5E")
      (fields (field (name "MANUFACTURER_PART_NUMBER") "0603WAF1002T5E"))
      (libsource (lib "") (part "R0603_1"))
    )
    (comp (ref "R35")
      (value "10K")
      (footprint "RESC1608X55N")
      (description "Resistor 0603WAF1002T5E")
      (fields (field (name "MANUFACTURER_PART_NUMBER") "0603WAF1002T5E"))
      (libsource (lib "") (part "R0603_1"))
    )
    (comp (ref "R36")
      (value "5.1K")
      (footprint "RESC1608X55N")
      (description "Resistor 0603WAF1002T5E")
      (fields (field (name "MANUFACTURER_PART_NUMBER") "0603WAF1002T5E"))
      (libsource (lib "Resistor^Capacitor^Inductor") (part "R0603"))
    )
    (comp (ref "R37")
      (value "NC")
      (footprint "RESC1608X55N")
      (description "Resistor 0603WAF1002T5E")
      (fields (field (name "MANUFACTURER_PART_NUMBER") "0603WAF1002T5E"))
      (libsource (lib "Resistor^Capacitor^Inductor") (part "R0603"))
    )
    (comp (ref "R38")
      (value "0Ω")
      (footprint "RESC1608X55N")
      (description "Resistor 0603WAF1002T5E")
      (fields (field (name "MANUFACTURER_PART_NUMBER") "0603WAF1002T5E"))
      (libsource (lib "Resistor^Capacitor^Inductor") (part "R0603"))
    )
    (comp (ref "R39")
      (value "0Ω")
      (footprint "RESC1608X55N")
      (description "Resistor 0603WAF1002T5E")
      (fields (field (name "MANUFACTURER_PART_NUMBER") "0603WAF1002T5E"))
      (libsource (lib "Resistor^Capacitor^Inductor") (part "R0603"))
    )
    (comp (ref "R40")
      (value "0Ω")
      (footprint "RESC1608X55N")
      (description "Resistor 0603WAF1002T5E")
      (fields (field (name "MANUFACTURER_PART_NUMBER") "0603WAF1002T5E"))
      (libsource (lib "Resistor^Capacitor^Inductor") (part "R0603"))
    )
    (comp (ref "RF1") (value "CA-C03") (footprint "CA-C03") (libsource (lib "Connector") (part "CA-C03")))
    (comp (ref "RT1")
      (value "NCP18XH103F03RB")
      (footprint "THRMC1608X95N")
      (description "Thermistor")
      (fields (field (name "MOUSER PART NUMBER") "81-NCP18XH103F03RB"))
      (libsource (lib "Resistor^Capacitor^Inductor") (part "NCP18XH103F03RB"))
    )
    (comp (ref "S1")
      (value "SGM3157")
      (footprint "SOT65P230X110-6N")
      (description "Switch")
      (fields (field (name "MANUFACTURER_PART_NUMBER") "SGM3157YC6/TR"))
      (libsource (lib "Switch^Relay") (part "SGM3157"))
    )
    (comp (ref "SW1")
      (value "TS-1088-AR02016")
      (footprint "TS1088AR02016")
      (description "Switch")
      (libsource (lib "Switch^Relay") (part "TS-1088-AR02016"))
    )
    (comp (ref "SW2")
      (value "TS-1088-AR02016")
      (footprint "TS1088AR02016")
      (description "Switch")
      (libsource (lib "Switch^Relay") (part "TS-1088-AR02016"))
    )
    (comp (ref "SW3")
      (value "TS-1088-AR02016")
      (footprint "TS1088AR02016")
      (description "Switch")
      (libsource (lib "Switch^Relay") (part "TS-1088-AR02016"))
    )
    (comp (ref "SW4")
      (value "TS-1088-AR02016")
      (footprint "TS1088AR02016")
      (description "Switch")
      (libsource (lib "Switch^Relay") (part "TS-1088-AR02016"))
    )
    (comp (ref "SW5")
      (value "TS-1088-AR02016")
      (footprint "TS1088AR02016")
      (description "Switch")
      (libsource (lib "Switch^Relay") (part "TS-1088-AR02016"))
    )
    (comp (ref "USB1")
      (value "TYPE-C 16PIN 2MD(073)")
      (footprint "USB-C-SMD_TYPE-C-6PIN-2MD-073")
      (fields (field (name "MANUFACTURER") "SHOU HAN(首韩)"))
      (libsource (lib "Connector") (part "TYPE-C 16PIN 2MD(073)"))
    )
    (comp (ref "Y1")
      (value "X322516MLB4SI")
      (footprint "X322516MLB4SI")
      (description "Crystal or Oscillator")
      (libsource (lib "Crystals") (part "X322516MLB4SI"))
    )
    (comp (ref "Y2")
      (value "X322540MPB4SI")
      (footprint "X322540MPB4SI")
      (description "Crystal or Oscillator")
      (libsource (lib "Crystals") (part "X322540MPB4SI"))
    )
  )
  (nets
    (net (code "1") (name "/ADC1_PTA11") (class "Default")
      (node (ref "IC1") (pin "160") (pinfunction "PTA11_160") (pintype "passive"))
      (node (ref "R10") (pin "2") (pinfunction "2_2") (pintype "passive"))
      (node (ref "RT1") (pin "1") (pinfunction "1_1") (pintype "passive"))
    )
    (net (code "2") (name "/CAN0_RX_PTA6") (class "Default")
      (node (ref "IC1") (pin "102") (pinfunction "PTA6_102") (pintype "passive"))
      (node (ref "IC3") (pin "4") (pinfunction "RXD_4") (pintype "passive"))
    )
    (net (code "3") (name "/CAN0_STB") (class "Default")
      (node (ref "IC1") (pin "101") (pinfunction "PTC30_101") (pintype "passive"))
      (node (ref "IC3") (pin "8") (pinfunction "STB_8") (pintype "passive"))
    )
    (net (code "4") (name "/CAN0_TX_PTA7") (class "Default")
      (node (ref "IC1") (pin "100") (pinfunction "PTA7_100") (pintype "passive"))
      (node (ref "IC3") (pin "1") (pinfunction "TXD_1") (pintype "passive"))
    )
    (net (code "5") (name "/CAN_H") (class "Default")
      (node (ref "IC3") (pin "7") (pinfunction "CANH_7") (pintype "passive"))
      (node (ref "J2") (pin "1") (pinfunction "1_1") (pintype "passive"))
      (node (ref "R31") (pin "2") (pinfunction "2_2") (pintype "passive"))
    )
    (net (code "6") (name "/CAN_L") (class "Default")
      (node (ref "IC3") (pin "6") (pinfunction "CANL_6") (pintype "passive"))
      (node (ref "J2") (pin "2") (pinfunction "2_2") (pintype "passive"))
      (node (ref "R31") (pin "1") (pinfunction "1_1") (pintype "passive"))
    )
    (net (code "7") (name "/CC1") (class "Default")
      (node (ref "R32") (pin "1") (pinfunction "1_1") (pintype "passive"))
      (node (ref "USB1") (pin "4") (pinfunction "CC1_4") (pintype "passive"))
    )
    (net (code "8") (name "/CC2") (class "Default")
      (node (ref "R36") (pin "1") (pinfunction "1_1") (pintype "passive"))
      (node (ref "USB1") (pin "10") (pinfunction "CC2_10") (pintype "passive"))
    )
    (net (code "9") (name "/DIO_I") (class "Default")
      (node (ref "IC6") (pin "40") (pinfunction "GPIO35_40") (pintype "passive"))
      (node (ref "S1") (pin "1") (pinfunction "B1_1") (pintype "passive"))
    )
    (net (code "10") (name "/DIO_O") (class "Default")
      (node (ref "IC6") (pin "37") (pinfunction "SPICLK_P_37") (pintype "passive"))
      (node (ref "S1") (pin "3") (pinfunction "B0_3") (pintype "passive"))
    )
    (net (code "11") (name "/DIO_SELECT") (class "Default")
      (node (ref "IC6") (pin "41") (pinfunction "GPIO36_41") (pintype "passive"))
      (node (ref "R37") (pin "1") (pinfunction "1_1") (pintype "passive"))
      (node (ref "S1") (pin "6") (pinfunction "Select_6") (pintype "passive"))
    )
    (net (code "12") (name "/EEPROM_WP_PTB18") (class "Default")
      (node (ref "IC1") (pin "42") (pinfunction "PTB18_42") (pintype "passive"))
      (node (ref "IC4") (pin "7") (pinfunction "WP_7") (pintype "passive"))
    )
    (net (code "13") (name "/ESP32S3_EN") (class "Default")
      (node (ref "IC1") (pin "172") (pinfunction "PTA8_172") (pintype "passive"))
      (node (ref "IC5") (pin "4") (pinfunction "Q_4") (pintype "passive"))
      (node (ref "IC6") (pin "4") (pinfunction "CHIP_PU_4") (pintype "passive"))
    )
    (net (code "14") (name "/ESP32S3_EN_RESET") (class "Default")
      (node (ref "IC1") (pin "171") (pinfunction "PTA9_171") (pintype "passive"))
      (node (ref "IC5") (pin "1") (pinfunction "LE_1") (pintype "passive"))
      (node (ref "R35") (pin "2") (pinfunction "2_2") (pintype "passive"))
    )
    (net (code "15") (name "/ESP32S3_EN_SET") (class "Default")
      (node (ref "IC1") (pin "163") (pinfunction "PTE0_163") (pintype "passive"))
      (node (ref "IC5") (pin "3") (pinfunction "D_3") (pintype "passive"))
      (node (ref "R34") (pin "2") (pinfunction "2_2") (pintype "passive"))
    )
    (net (code "16") (name "/EXTAL") (class "Default")
      (node (ref "C16") (pin "2") (pinfunction "2_2") (pintype "passive"))
      (node (ref "IC1") (pin "23") (pinfunction "EXTAL_23") (pintype "passive"))
      (node (ref "Y1") (pin "3") (pinfunction "OSC2_3") (pintype "passive"))
    )
    (net (code "17") (name "/INT_TLF35584_PTD6") (class "Default")
      (node (ref "IC1") (pin "52") (pinfunction "PTD6_52") (pintype "passive"))
      (node (ref "R20") (pin "1") (pinfunction "1_1") (pintype "passive"))
    )
    (net (code "18") (name "/KEY_GPIO0") (class "Default")
      (node (ref "IC6") (pin "5") (pinfunction "GPIO0_5") (pintype "passive"))
      (node (ref "SW4") (pin "1") (pinfunction "COMMON_1") (pintype "passive"))
    )
    (net (code "19") (name "/KEY_GPIO21") (class "Default")
      (node (ref "IC6") (pin "27") (pinfunction "GPIO21_27") (pintype "passive"))
      (node (ref "SW5") (pin "1") (pinfunction "COMMON_1") (pintype "passive"))
    )
    (net (code "20") (name "/LED_PTA29") (class "Default")
      (node (ref "IC1") (pin "32") (pinfunction "PTA29_32") (pintype "passive"))
      (node (ref "LED1") (pin "1") (pinfunction "K_1") (pintype "passive"))
    )
    (net (code "21") (name "/LED_PTA30") (class "Default")
      (node (ref "IC1") (pin "33") (pinfunction "PTA30_33") (pintype "passive"))
      (node (ref "LED2") (pin "1") (pinfunction "K_1") (pintype "passive"))
    )
    (net (code "22") (name "/LED_PTA31") (class "Default")
      (node (ref "IC1") (pin "39") (pinfunction "PTA31_39") (pintype "passive"))
      (node (ref "LED3") (pin "1") (pinfunction "-_1") (pintype "passive"))
    )
    (net (code "23") (name "/LNA") (class "Default")
      (node (ref "IC6") (pin "1") (pinfunction "LNA_IN_1") (pintype "passive"))
      (node (ref "R39") (pin "1") (pinfunction "1_1") (pintype "passive"))
    )
    (net (code "24") (name "/LPI2C0_SCL_EEPROM") (class "Default")
      (node (ref "IC1") (pin "40") (pinfunction "PTD14_40") (pintype "passive"))
      (node (ref "IC4") (pin "6") (pinfunction "SCL_6") (pintype "passive"))
      (node (ref "R29") (pin "1") (pinfunction "1_1") (pintype "passive"))
    )
    (net (code "25") (name "/LPI2C0_SDA_EEPROM") (class "Default")
      (node (ref "IC1") (pin "41") (pinfunction "PTD13_41") (pintype "passive"))
      (node (ref "IC4") (pin "5") (pinfunction "SDA_5") (pintype "passive"))
      (node (ref "R30") (pin "1") (pinfunction "1_1") (pintype "passive"))
    )
    (net (code "26") (name "/LPSPI1_SCL") (class "Default")
      (node (ref "IC1") (pin "114") (pinfunction "PTB14_114") (pintype "passive"))
      (node (ref "R15") (pin "1") (pinfunction "1_1") (pintype "passive"))
    )
    (net (code "27") (name "/LPSPI1_SCS") (class "Default")
      (node (ref "IC1") (pin "110") (pinfunction "PTB17_110") (pintype "passive"))
      (node (ref "R16") (pin "1") (pinfunction "1_1") (pintype "passive"))
    )
    (net (code "28") (name "/LPSPI1_SDI") (class "Default")
      (node (ref "IC1") (pin "112") (pinfunction "PTB16_112") (pintype "passive"))
      (node (ref "R12") (pin "1") (pinfunction "1_1") (pintype "passive"))
    )
    (net (code "29") (name "/LPSPI1_SDO") (class "Default")
      (node (ref "IC1") (pin "113") (pinfunction "PTB15_113") (pintype "passive"))
      (node (ref "R13") (pin "1") (pinfunction "1_1") (pintype "passive"))
    )
    (net (code "30") (name "/LPUART6_RX") (class "Default")
      (node (ref "IC1") (pin "145") (pinfunction "PTA15_145") (pintype "passive"))
      (node (ref "IC6") (pin "48") (pinfunction "MTMS_48") (pintype "passive"))
      (node (ref "J1") (pin "10") (pinfunction "10_10") (pintype "passive"))
    )
    (net (code "31") (name "/LPUART6_TX") (class "Default")
      (node (ref "IC1") (pin "143") (pinfunction "PTA16_143") (pintype "passive"))
      (node (ref "IC6") (pin "47") (pinfunction "MTDI_47") (pintype "passive"))
      (node (ref "J1") (pin "8") (pinfunction "8_8") (pintype "passive"))
    )
    (net (code "32") (name "/MPS_TLF35584_PTD5") (class "Default")
      (node (ref "IC1") (pin "53") (pinfunction "PTD5_53") (pintype "passive"))
      (node (ref "IC2") (pin "22") (pinfunction "MPS_22") (pintype "passive"))
      (node (ref "R18") (pin "2") (pinfunction "2_2") (pintype "passive"))
    )
    (net (code "33") (name "/PTA0") (class "Default")
      (node (ref "BTB1") (pin "21") (pinfunction "21_21") (pintype "passive"))
      (node (ref "IC1") (pin "137") (pinfunction "PTA0_137") (pintype "passive"))
    )
    (net (code "34") (name "/PTA1") (class "Default")
      (node (ref "BTB1") (pin "23") (pinfunction "23_23") (pintype "passive"))
      (node (ref "IC1") (pin "135") (pinfunction "PTA1_135") (pintype "passive"))
    )
    (net (code "35") (name "/PTA2") (class "Default")
      (node (ref "BTB1") (pin "37") (pinfunction "37_37") (pintype "passive"))
      (node (ref "IC1") (pin "124") (pinfunction "PTA2_124") (pintype "passive"))
    )
    (net (code "36") (name "/PTA3") (class "Default")
      (node (ref "BTB1") (pin "36") (pinfunction "36_36") (pintype "passive"))
      (node (ref "IC1") (pin "123") (pinfunction "PTA3_123") (pintype "passive"))
    )
    (net (code "37") (name "/PTA12") (class "Default")
      (node (ref "BTB1") (pin "5") (pinfunction "5_5") (pintype "passive"))
      (node (ref "IC1") (pin "159") (pinfunction "PTA12_159") (pintype "passive"))
    )
    (net (code "38") (name "/PTA13") (class "Default")
      (node (ref "BTB1") (pin "9") (pinfunction "9_9") (pintype "passive"))
      (node (ref "IC1") (pin "155") (pinfunction "PTA13_155") (pintype "passive"))
    )
    (net (code "39") (name "/PTA14") (class "Default")
      (node (ref "BTB1") (pin "12") (pinfunction "12_12") (pintype "passive"))
      (node (ref "IC1") (pin "152") (pinfunction "PTA14_152") (pintype "passive"))
    )
    (net (code "40") (name "/PTA17") (class "Default")
      (node (ref "BTB1") (pin "46") (pinfunction "46_46") (pintype "passive"))
      (node (ref "IC1") (pin "109") (pinfunction "PTA17_109") (pintype "passive"))
    )
    (net (code "41") (name "/PTA18") (class "Default")
      (node (ref "BTB1") (pin "2") (pinfunction "2_2") (pintype "passive"))
      (node (ref "IC1") (pin "1") (pinfunction "PTA18_1") (pintype "passive"))
    )
    (net (code "42") (name "/PTA19") (class "Default")
      (node (ref "BTB1") (pin "1") (pinfunction "1_1") (pintype "passive"))
      (node (ref "IC1") (pin "2") (pinfunction "PTA19_2") (pintype "passive"))
    )
    (net (code "43") (name "/PTA20") (class "Default")
      (node (ref "BTB1") (pin "54") (pinfunction "54_54") (pintype "passive"))
      (node (ref "IC1") (pin "3") (pinfunction "PTA20_3") (pintype "passive"))
    )
    (net (code "44") (name "/PTA21") (class "Default")
      (node (ref "BTB1") (pin "57") (pinfunction "57_57") (pintype "passive"))
      (node (ref "IC1") (pin "6") (pinfunction "PTA21_6") (pintype "passive"))
    )
    (net (code "45") (name "/PTA24") (class "Default")
      (node (ref "BTB1") (pin "49") (pinfunction "49_49") (pintype "passive"))
      (node (ref "IC1") (pin "14") (pinfunction "PTA24_14") (pintype "passive"))
    )
    (net (code "46") (name "/PTA25") (class "Default")
      (node (ref "BTB1") (pin "48") (pinfunction "48_48") (pintype "passive"))
      (node (ref "IC1") (pin "15") (pinfunction "PTA25_15") (pintype "passive"))
    )
    (net (code "47") (name "/PTA27") (class "Default")
      (node (ref "BTB1") (pin "47") (pinfunction "47_47") (pintype "passive"))
      (node (ref "IC1") (pin "28") (pinfunction "PTA27_28") (pintype "passive"))
    )
    (net (code "48") (name "/PTA28") (class "Default")
      (node (ref "BTB2") (pin "9") (pinfunction "9_9") (pintype "passive"))
      (node (ref "IC1") (pin "30") (pinfunction "PTA28_30") (pintype "passive"))
    )
    (net (code "49") (name "/PTB0") (class "Default")
      (node (ref "BTB2") (pin "19") (pinfunction "19_19") (pintype "passive"))
      (node (ref "IC1") (pin "95") (pinfunction "PTB0_95") (pintype "passive"))
    )
    (net (code "50") (name "/PTB1") (class "Default")
      (node (ref "BTB2") (pin "27") (pinfunction "27_27") (pintype "passive"))
      (node (ref "IC1") (pin "94") (pinfunction "PTB1_94") (pintype "passive"))
    )
    (net (code "51") (name "/PTB2") (class "Default")
      (node (ref "BTB2") (pin "40") (pinfunction "40_40") (pintype "passive"))
      (node (ref "IC1") (pin "79") (pinfunction "PTB2_79") (pintype "passive"))
    )
    (net (code "52") (name "/PTB3") (class "Default")
      (node (ref "BTB2") (pin "43") (pinfunction "43_43") (pintype "passive"))
      (node (ref "IC1") (pin "74") (pinfunction "PTB3_74") (pintype "passive"))
    )
    (net (code "53") (name "/PTB4") (class "Default")
      (node (ref "BTB2") (pin "5") (pinfunction "5_5") (pintype "passive"))
      (node (ref "IC1") (pin "48") (pinfunction "PTB4_48") (pintype "passive"))
    )
    (net (code "54") (name "/PTB5") (class "Default")
      (node (ref "BTB2") (pin "4") (pinfunction "4_4") (pintype "passive"))
      (node (ref "IC1") (pin "47") (pinfunction "PTB5_47") (pintype "passive"))
    )
    (net (code "55") (name "/PTB8") (class "Default")
      (node (ref "BTB1") (pin "25") (pinfunction "25_25") (pintype "passive"))
      (node (ref "IC1") (pin "133") (pinfunction "PTB8_133") (pintype "passive"))
    )
    (net (code "56") (name "/PTB9") (class "Default")
      (node (ref "BTB1") (pin "28") (pinfunction "28_28") (pintype "passive"))
      (node (ref "IC1") (pin "130") (pinfunction "PTB9_130") (pintype "passive"))
    )
    (net (code "57") (name "/PTB10") (class "Default")
      (node (ref "BTB1") (pin "29") (pinfunction "29_29") (pintype "passive"))
      (node (ref "IC1") (pin "129") (pinfunction "PTB10_129") (pintype "passive"))
    )
    (net (code "58") (name "/PTB11") (class "Default")
      (node (ref "BTB1") (pin "39") (pinfunction "39_39") (pintype "passive"))
      (node (ref "IC1") (pin "126") (pinfunction "PTB11_126") (pintype "passive"))
    )
    (net (code "59") (name "/PTB12") (class "Default")
      (node (ref "BTB1") (pin "42") (pinfunction "42_42") (pintype "passive"))
      (node (ref "IC1") (pin "117") (pinfunction "PTB12_117") (pintype "passive"))
    )
    (net (code "60") (name "/PTB13") (class "Default")
      (node (ref "BTB1") (pin "43") (pinfunction "43_43") (pintype "passive"))
      (node (ref "IC1") (pin "116") (pinfunction "PTB13_116") (pintype "passive"))
    )
    (net (code "61") (name "/PTB20") (class "Default")
      (node (ref "BTB2") (pin "1") (pinfunction "1_1") (pintype "passive"))
      (node (ref "IC1") (pin "44") (pinfunction "PTB20_44") (pintype "passive"))
    )
    (net (code "62") (name "/PTB21") (class "Default")
      (node (ref "BTB2") (pin "2") (pinfunction "2_2") (pintype "passive"))
      (node (ref "IC1") (pin "45") (pinfunction "PTB21_45") (pintype "passive"))
    )
    (net (code "63") (name "/PTB22") (class "Default")
      (node (ref "BTB2") (pin "49") (pinfunction "49_49") (pintype "passive"))
      (node (ref "IC1") (pin "67") (pinfunction "PTB22_67") (pintype "passive"))
    )
    (net (code "64") (name "/PTB23") (class "Default")
      (node (ref "BTB2") (pin "47") (pinfunction "47_47") (pintype "passive"))
      (node (ref "IC1") (pin "69") (pinfunction "PTB23_69") (pintype "passive"))
    )
    (net (code "65") (name "/PTB24") (class "Default")
      (node (ref "BTB2") (pin "46") (pinfunction "46_46") (pintype "passive"))
      (node (ref "IC1") (pin "70") (pinfunction "PTB24_70") (pintype "passive"))
    )
    (net (code "66") (name "/PTB25") (class "Default")
      (node (ref "BTB2") (pin "44") (pinfunction "44_44") (pintype "passive"))
      (node (ref "IC1") (pin "72") (pinfunction "PTB25_72") (pintype "passive"))
    )
    (net (code "67") (name "/PTB27") (class "Default")
      (node (ref "BTB2") (pin "42") (pinfunction "42_42") (pintype "passive"))
      (node (ref "IC1") (pin "75") (pinfunction "PTB27_75") (pintype "passive"))
    )
    (net (code "68") (name "/PTB28") (class "Default")
      (node (ref "BTB2") (pin "41") (pinfunction "41_41") (pintype "passive"))
      (node (ref "IC1") (pin "76") (pinfunction "PTB28_76") (pintype "passive"))
    )
    (net (code "69") (name "/PTB29") (class "Default")
      (node (ref "BTB2") (pin "39") (pinfunction "39_39") (pintype "passive"))
      (node (ref "IC1") (pin "80") (pinfunction "PTB29_80") (pintype "passive"))
    )
    (net (code "70") (name "/PTC0") (class "Default")
      (node (ref "BTB2") (pin "54") (pinfunction "54_54") (pintype "passive"))
      (node (ref "IC1") (pin "62") (pinfunction "PTC0_62") (pintype "passive"))
    )
    (net (code "71") (name "/PTC1") (class "Default")
      (node (ref "BTB2") (pin "55") (pinfunction "55_55") (pintype "passive"))
      (node (ref "IC1") (pin "61") (pinfunction "PTC1_61") (pintype "passive"))
    )
    (net (code "72") (name "/PTC2") (class "Default")
      (node (ref "BTB2") (pin "59") (pinfunction "59_59") (pintype "passive"))
      (node (ref "IC1") (pin "50") (pinfunction "PTC2_50") (pintype "passive"))
    )
    (net (code "73") (name "/PTC3") (class "Default")
      (node (ref "BTB2") (pin "60") (pinfunction "60_60") (pintype "passive"))
      (node (ref "IC1") (pin "49") (pinfunction "PTC3_49") (pintype "passive"))
    )
    (net (code "74") (name "/PTC6") (class "Default")
      (node (ref "BTB1") (pin "17") (pinfunction "17_17") (pintype "passive"))
      (node (ref "IC1") (pin "141") (pinfunction "PTC6_141") (pintype "passive"))
    )
    (net (code "75") (name "/PTC7") (class "Default")
      (node (ref "BTB1") (pin "18") (pinfunction "18_18") (pintype "passive"))
      (node (ref "IC1") (pin "140") (pinfunction "PTC7_140") (pintype "passive"))
    )
    (net (code "76") (name "/PTC8") (class "Default")
      (node (ref "BTB2") (pin "16") (pinfunction "16_16") (pintype "passive"))
      (node (ref "IC1") (pin "98") (pinfunction "PTC8_98") (pintype "passive"))
    )
    (net (code "77") (name "/PTC9") (class "Default")
      (node (ref "BTB2") (pin "17") (pinfunction "17_17") (pintype "passive"))
      (node (ref "IC1") (pin "97") (pinfunction "PTC9_97") (pintype "passive"))
    )
    (net (code "78") (name "/PTC10") (class "Default")
      (node (ref "BTB2") (pin "25") (pinfunction "25_25") (pintype "passive"))
      (node (ref "IC1") (pin "92") (pinfunction "PTC10_92") (pintype "passive"))
    )
    (net (code "79") (name "/PTC11") (class "Default")
      (node (ref "BTB2") (pin "23") (pinfunction "23_23") (pintype "passive"))
      (node (ref "IC1") (pin "90") (pinfunction "PTC11_90") (pintype "passive"))
    )
    (net (code "80") (name "/PTC12") (class "Default")
      (node (ref "BTB2") (pin "36") (pinfunction "36_36") (pintype "passive"))
      (node (ref "IC1") (pin "83") (pinfunction "PTC12_83") (pintype "passive"))
    )
    (net (code "81") (name "/PTC13") (class "Default")
      (node (ref "BTB2") (pin "38") (pinfunction "38_38") (pintype "passive"))
      (node (ref "IC1") (pin "81") (pinfunction "PTC13_81") (pintype "passive"))
    )
    (net (code "82") (name "/PTC14") (class "Default")
      (node (ref "BTB2") (pin "45") (pinfunction "45_45") (pintype "passive"))
      (node (ref "IC1") (pin "71") (pinfunction "PTC14_71") (pintype "passive"))
    )
    (net (code "83") (name "/PTC15") (class "Default")
      (node (ref "BTB2") (pin "48") (pinfunction "48_48") (pintype "passive"))
      (node (ref "IC1") (pin "68") (pinfunction "PTC15_68") (pintype "passive"))
    )
    (net (code "84") (name "/PTC16") (class "Default")
      (node (ref "BTB2") (pin "50") (pinfunction "50_50") (pintype "passive"))
      (node (ref "IC1") (pin "66") (pinfunction "PTC16_66") (pintype "passive"))
    )
    (net (code "85") (name "/PTC17") (class "Default")
      (node (ref "BTB2") (pin "51") (pinfunction "51_51") (pintype "passive"))
      (node (ref "IC1") (pin "65") (pinfunction "PTC17_65") (pintype "passive"))
    )
    (net (code "86") (name "/PTC18") (class "Default")
      (node (ref "BTB2") (pin "37") (pinfunction "37_37") (pintype "passive"))
      (node (ref "IC1") (pin "82") (pinfunction "PTC18_82") (pintype "passive"))
    )
    (net (code "87") (name "/PTC19") (class "Default")
      (node (ref "BTB2") (pin "35") (pinfunction "35_35") (pintype "passive"))
      (node (ref "IC1") (pin "84") (pinfunction "PTC19_84") (pintype "passive"))
    )
    (net (code "88") (name "/PTC20") (class "Default")
      (node (ref "BTB2") (pin "34") (pinfunction "34_34") (pintype "passive"))
      (node (ref "IC1") (pin "85") (pinfunction "PTC20_85") (pintype "passive"))
    )
    (net (code "89") (name "/PTC21") (class "Default")
      (node (ref "BTB2") (pin "33") (pinfunction "33_33") (pintype "passive"))
      (node (ref "IC1") (pin "86") (pinfunction "PTC21_86") (pintype "passive"))
    )
    (net (code "90") (name "/PTC23") (class "Default")
      (node (ref "BTB2") (pin "20") (pinfunction "20_20") (pintype "passive"))
      (node (ref "IC1") (pin "87") (pinfunction "PTC23_87") (pintype "passive"))
    )
    (net (code "91") (name "/PTC24") (class "Default")
      (node (ref "BTB2") (pin "21") (pinfunction "21_21") (pintype "passive"))
      (node (ref "IC1") (pin "88") (pinfunction "PTC24_88") (pintype "passive"))
    )
    (net (code "92") (name "/PTC25") (class "Default")
      (node (ref "BTB2") (pin "22") (pinfunction "22_22") (pintype "passive"))
      (node (ref "IC1") (pin "89") (pinfunction "PTC25_89") (pintype "passive"))
    )
    (net (code "93") (name "/PTC26") (class "Default")
      (node (ref "BTB2") (pin "24") (pinfunction "24_24") (pintype "passive"))
      (node (ref "IC1") (pin "91") (pinfunction "PTC26_91") (pintype "passive"))
    )
    (net (code "94") (name "/PTC27") (class "Default")
      (node (ref "BTB2") (pin "26") (pinfunction "26_26") (pintype "passive"))
      (node (ref "IC1") (pin "93") (pinfunction "PTC27_93") (pintype "passive"))
    )
    (net (code "95") (name "/PTC28") (class "Default")
      (node (ref "BTB2") (pin "18") (pinfunction "18_18") (pintype "passive"))
      (node (ref "IC1") (pin "96") (pinfunction "PTC28_96") (pintype "passive"))
    )
    (net (code "96") (name "/PTC29") (class "Default")
      (node (ref "BTB2") (pin "15") (pinfunction "15_15") (pintype "passive"))
      (node (ref "IC1") (pin "99") (pinfunction "PTC29_99") (pintype "passive"))
    )
    (net (code "97") (name "/PTC31") (class "Default")
      (node (ref "BTB2") (pin "14") (pinfunction "14_14") (pintype "passive"))
      (node (ref "IC1") (pin "103") (pinfunction "PTC31_103") (pintype "passive"))
    )
    (net (code "98") (name "/PTD0") (class "Default")
      (node (ref "BTB1") (pin "59") (pinfunction "59_59") (pintype "passive"))
      (node (ref "IC1") (pin "8") (pinfunction "PTD0_8") (pintype "passive"))
    )
    (net (code "99") (name "/PTD1") (class "Default")
      (node (ref "BTB1") (pin "58") (pinfunction "58_58") (pintype "passive"))
      (node (ref "IC1") (pin "7") (pinfunction "PTD1_7") (pintype "passive"))
    )
    (net (code "100") (name "/PTD2") (class "Default")
      (node (ref "BTB1") (pin "34") (pinfunction "34_34") (pintype "passive"))
      (node (ref "IC1") (pin "121") (pinfunction "PTD2_121") (pintype "passive"))
    )
    (net (code "101") (name "/PTD3") (class "Default")
      (node (ref "BTB1") (pin "33") (pinfunction "33_33") (pintype "passive"))
      (node (ref "IC1") (pin "120") (pinfunction "PTD3_120") (pintype "passive"))
    )
    (net (code "102") (name "/PTD4") (class "Default")
      (node (ref "BTB1") (pin "40") (pinfunction "40_40") (pintype "passive"))
      (node (ref "IC1") (pin "119") (pinfunction "PTD4_119") (pintype "passive"))
    )
    (net (code "103") (name "/PTD8") (class "Default")
      (node (ref "BTB2") (pin "52") (pinfunction "52_52") (pintype "passive"))
      (node (ref "IC1") (pin "64") (pinfunction "PTD8_64") (pintype "passive"))
    )
    (net (code "104") (name "/PTD9") (class "Default")
      (node (ref "BTB2") (pin "53") (pinfunction "53_53") (pintype "passive"))
      (node (ref "IC1") (pin "63") (pinfunction "PTD9_63") (pintype "passive"))
    )
    (net (code "105") (name "/PTD10") (class "Default")
      (node (ref "BTB2") (pin "56") (pinfunction "56_56") (pintype "passive"))
      (node (ref "IC1") (pin "56") (pinfunction "PTD10_56") (pintype "passive"))
    )
    (net (code "106") (name "/PTD11") (class "Default")
      (node (ref "BTB2") (pin "57") (pinfunction "57_57") (pintype "passive"))
      (node (ref "IC1") (pin "55") (pinfunction "PTD11_55") (pintype "passive"))
    )
    (net (code "107") (name "/PTD12") (class "Default")
      (node (ref "BTB2") (pin "58") (pinfunction "58_58") (pintype "passive"))
      (node (ref "IC1") (pin "54") (pinfunction "PTD12_54") (pintype "passive"))
    )
    (net (code "108") (name "/PTD15") (class "Default")
      (node (ref "BTB2") (pin "6") (pinfunction "6_6") (pintype "passive"))
      (node (ref "IC1") (pin "35") (pinfunction "PTD15_35") (pintype "passive"))
    )
    (net (code "109") (name "/PTD16") (class "Default")
      (node (ref "BTB2") (pin "7") (pinfunction "7_7") (pintype "passive"))
      (node (ref "IC1") (pin "34") (pinfunction "PTD16_34") (pintype "passive"))
    )
    (net (code "110") (name "/PTD17") (class "Default")
      (node (ref "BTB2") (pin "8") (pinfunction "8_8") (pintype "passive"))
      (node (ref "IC1") (pin "31") (pinfunction "PTD17_31") (pintype "passive"))
    )
    (net (code "111") (name "/PTD20") (class "Default")
      (node (ref "BTB1") (pin "45") (pinfunction "45_45") (pintype "passive"))
      (node (ref "IC1") (pin "111") (pinfunction "PTD20_111") (pintype "passive"))
    )
    (net (code "112") (name "/PTD21") (class "Default")
      (node (ref "BTB1") (pin "44") (pinfunction "44_44") (pintype "passive"))
      (node (ref "IC1") (pin "115") (pinfunction "PTD21_115") (pintype "passive"))
    )
    (net (code "113") (name "/PTD22") (class "Default")
      (node (ref "BTB1") (pin "41") (pinfunction "41_41") (pintype "passive"))
      (node (ref "IC1") (pin "118") (pinfunction "PTD22_118") (pintype "passive"))
    )
    (net (code "114") (name "/PTD23") (class "Default")
      (node (ref "BTB1") (pin "35") (pinfunction "35_35") (pintype "passive"))
      (node (ref "IC1") (pin "122") (pinfunction "PTD23_122") (pintype "passive"))
    )
    (net (code "115") (name "/PTD24") (class "Default")
      (node (ref "BTB1") (pin "38") (pinfunction "38_38") (pintype "passive"))
      (node (ref "IC1") (pin "125") (pinfunction "PTD24_125") (pintype "passive"))
    )
    (net (code "116") (name "/PTD26") (class "Default")
      (node (ref "BTB1") (pin "27") (pinfunction "27_27") (pintype "passive"))
      (node (ref "IC1") (pin "131") (pinfunction "PTD26_131") (pintype "passive"))
    )
    (net (code "117") (name "/PTD27") (class "Default")
      (node (ref "BTB1") (pin "26") (pinfunction "26_26") (pintype "passive"))
      (node (ref "IC1") (pin "132") (pinfunction "PTD27_132") (pintype "passive"))
    )
    (net (code "118") (name "/PTD28") (class "Default")
      (node (ref "BTB1") (pin "24") (pinfunction "24_24") (pintype "passive"))
      (node (ref "IC1") (pin "134") (pinfunction "PTD28_134") (pintype "passive"))
    )
    (net (code "119") (name "/PTD29") (class "Default")
      (node (ref "BTB1") (pin "22") (pinfunction "22_22") (pintype "passive"))
      (node (ref "IC1") (pin "136") (pinfunction "PTD29_136") (pintype "passive"))
    )
    (net (code "120") (name "/PTD30") (class "Default")
      (node (ref "BTB1") (pin "20") (pinfunction "20_20") (pintype "passive"))
      (node (ref "IC1") (pin "138") (pinfunction "PTD30_138") (pintype "passive"))
    )
    (net (code "121") (name "/PTD31") (class "Default")
      (node (ref "BTB1") (pin "19") (pinfunction "19_19") (pintype "passive"))
      (node (ref "IC1") (pin "139") (pinfunction "PTD31_139") (pintype "passive"))
    )
    (net (code "122") (name "/PTE1") (class "Default")
      (node (ref "BTB1") (pin "4") (pinfunction "4_4") (pintype "passive"))
      (node (ref "IC1") (pin "162") (pinfunction "PTE1_162") (pintype "passive"))
    )
    (net (code "123") (name "/PTE2") (class "Default")
      (node (ref "BTB1") (pin "13") (pinfunction "13_13") (pintype "passive"))
      (node (ref "IC1") (pin "147") (pinfunction "PTE2_147") (pintype "passive"))
    )
    (net (code "124") (name "/PTE3") (class "Default")
      (node (ref "BTB2") (pin "11") (pinfunction "11_11") (pintype "passive"))
      (node (ref "IC1") (pin "27") (pinfunction "PTE3_27") (pintype "passive"))
    )
    (net (code "125") (name "/PTE4") (class "Default")
      (node (ref "BTB1") (pin "50") (pinfunction "50_50") (pintype "passive"))
      (node (ref "IC1") (pin "13") (pinfunction "PTE4_13") (pintype "passive"))
    )
    (net (code "126") (name "/PTE5") (class "Default")
      (node (ref "BTB1") (pin "51") (pinfunction "51_51") (pintype "passive"))
      (node (ref "IC1") (pin "12") (pinfunction "PTE5_12") (pintype "passive"))
    )
    (net (code "127") (name "/PTE6") (class "Default")
      (node (ref "BTB1") (pin "14") (pinfunction "14_14") (pintype "passive"))
      (node (ref "IC1") (pin "146") (pinfunction "PTE6_146") (pintype "passive"))
    )
    (net (code "128") (name "/PTE7") (class "Default")
      (node (ref "BTB2") (pin "13") (pinfunction "13_13") (pintype "passive"))
      (node (ref "IC1") (pin "104") (pinfunction "PTE7_104") (pintype "passive"))
    )
    (net (code "129") (name "/PTE8") (class "Default")
      (node (ref "BTB2") (pin "3") (pinfunction "3_3") (pintype "passive"))
      (node (ref "IC1") (pin "46") (pinfunction "PTE8_46") (pintype "passive"))
    )
    (net (code "130") (name "/PTE10") (class "Default")
      (node (ref "BTB1") (pin "52") (pinfunction "52_52") (pintype "passive"))
      (node (ref "IC1") (pin "10") (pinfunction "PTE10_10") (pintype "passive"))
    )
    (net (code "131") (name "/PTE11") (class "Default")
      (node (ref "BTB1") (pin "53") (pinfunction "53_53") (pintype "passive"))
      (node (ref "IC1") (pin "9") (pinfunction "PTE11_9") (pintype "passive"))
    )
    (net (code "132") (name "/PTE12") (class "Default")
      (node (ref "BTB2") (pin "10") (pinfunction "10_10") (pintype "passive"))
      (node (ref "IC1") (pin "29") (pinfunction "PTE12_29") (pintype "passive"))
    )
    (net (code "133") (name "/PTE14") (class "Default")
      (node (ref "BTB2") (pin "12") (pinfunction "12_12") (pintype "passive"))
      (node (ref "IC1") (pin "26") (pinfunction "PTE14_26") (pintype "passive"))
    )
    (net (code "134") (name "/PTE15") (class "Default")
      (node (ref "BTB1") (pin "56") (pinfunction "56_56") (pintype "passive"))
      (node (ref "IC1") (pin "5") (pinfunction "PTE15_5") (pintype "passive"))
    )
    (net (code "135") (name "/PTE16") (class "Default")
      (node (ref "BTB1") (pin "55") (pinfunction "55_55") (pintype "passive"))
      (node (ref "IC1") (pin "4") (pinfunction "PTE16_4") (pintype "passive"))
    )
    (net (code "136") (name "/PTE17") (class "Default")
      (node (ref "BTB1") (pin "16") (pinfunction "16_16") (pintype "passive"))
      (node (ref "IC1") (pin "142") (pinfunction "PTE17_142") (pintype "passive"))
    )
    (net (code "137") (name "/PTE18") (class "Default")
      (node (ref "BTB1") (pin "15") (pinfunction "15_15") (pintype "passive"))
      (node (ref "IC1") (pin "144") (pinfunction "PTE18_144") (pintype "passive"))
    )
    (net (code "138") (name "/PTE21") (class "Default")
      (node (ref "BTB1") (pin "11") (pinfunction "11_11") (pintype "passive"))
      (node (ref "IC1") (pin "153") (pinfunction "PTE21_153") (pintype "passive"))
    )
    (net (code "139") (name "/PTE22") (class "Default")
      (node (ref "BTB1") (pin "10") (pinfunction "10_10") (pintype "passive"))
      (node (ref "IC1") (pin "154") (pinfunction "PTE22_154") (pintype "passive"))
    )
    (net (code "140") (name "/PTE23") (class "Default")
      (node (ref "BTB1") (pin "8") (pinfunction "8_8") (pintype "passive"))
      (node (ref "IC1") (pin "156") (pinfunction "PTE23_156") (pintype "passive"))
    )
    (net (code "141") (name "/PTE24") (class "Default")
      (node (ref "BTB1") (pin "7") (pinfunction "7_7") (pintype "passive"))
      (node (ref "IC1") (pin "157") (pinfunction "PTE24_157") (pintype "passive"))
    )
    (net (code "142") (name "/PTE25") (class "Default")
      (node (ref "BTB1") (pin "6") (pinfunction "6_6") (pintype "passive"))
      (node (ref "IC1") (pin "158") (pinfunction "PTE25_158") (pintype "passive"))
    )
    (net (code "143") (name "/PTE26") (class "Default")
      (node (ref "BTB1") (pin "3") (pinfunction "3_3") (pintype "passive"))
      (node (ref "IC1") (pin "164") (pinfunction "PTE26_164") (pintype "passive"))
    )
    (net (code "144") (name "/RESET") (class "Default")
      (node (ref "C4") (pin "2") (pinfunction "2_2") (pintype "passive"))
      (node (ref "IC1") (pin "167") (pinfunction "PTA5_167") (pintype "passive"))
      (node (ref "IC6") (pin "45") (pinfunction "MTDO_45") (pintype "passive"))
      (node (ref "J1") (pin "6") (pinfunction "6_6") (pintype "passive"))
      (node (ref "R19") (pin "1") (pinfunction "1_1") (pintype "passive"))
      (node (ref "R5") (pin "1") (pinfunction "1_1") (pintype "passive"))
      (node (ref "SW1") (pin "2") (pinfunction "NO_2") (pintype "passive"))
    )
    (net (code "145") (name "/SW0_PTB19") (class "Default")
      (node (ref "IC1") (pin "43") (pinfunction "PTB19_43") (pintype "passive"))
      (node (ref "SW2") (pin "1") (pinfunction "COMMON_1") (pintype "passive"))
    )
    (net (code "146") (name "/SW1_PTB26") (class "Default")
      (node (ref "IC1") (pin "73") (pinfunction "PTB26_73") (pintype "passive"))
      (node (ref "SW3") (pin "1") (pinfunction "COMMON_1") (pintype "passive"))
    )
    (net (code "147") (name "/SWD_TDI") (class "Default")
      (node (ref "IC6") (pin "44") (pinfunction "MTCK_44") (pintype "passive"))
      (node (ref "R2") (pin "2") (pinfunction "2_2") (pintype "passive"))
    )
    (net (code "148") (name "/SWD_TDO") (class "Default")
      (node (ref "IC6") (pin "43") (pinfunction "GPIO38_43") (pintype "passive"))
      (node (ref "R1") (pin "2") (pinfunction "2_2") (pintype "passive"))
    )
    (net (code "149") (name "/TCK{slash}CLK") (class "Default")
      (node (ref "IC1") (pin "166") (pinfunction "PTC4_166") (pintype "passive"))
      (node (ref "IC6") (pin "42") (pinfunction "GPIO37_42") (pintype "passive"))
      (node (ref "J1") (pin "9") (pinfunction "9_9") (pintype "passive"))
      (node (ref "R7") (pin "2") (pinfunction "2_2") (pintype "passive"))
    )
    (net (code "150") (name "/TDI") (class "Default")
      (node (ref "IC1") (pin "165") (pinfunction "PTC5_165") (pintype "passive"))
      (node (ref "J1") (pin "4") (pinfunction "4_4") (pintype "passive"))
      (node (ref "R2") (pin "1") (pinfunction "1_1") (pintype "passive"))
    )
    (net (code "151") (name "/TDO") (class "Default")
      (node (ref "IC1") (pin "161") (pinfunction "PTA10_161") (pintype "passive"))
      (node (ref "J1") (pin "2") (pinfunction "2_2") (pintype "passive"))
      (node (ref "R1") (pin "1") (pinfunction "1_1") (pintype "passive"))
    )
    (net (code "152") (name "/TMS{slash}DIO") (class "Default")
      (node (ref "IC1") (pin "170") (pinfunction "PTA4_170") (pintype "passive"))
      (node (ref "J1") (pin "7") (pinfunction "7_7") (pintype "passive"))
      (node (ref "R37") (pin "2") (pinfunction "2_2") (pintype "passive"))
      (node (ref "S1") (pin "4") (pinfunction "A_4") (pintype "passive"))
    )
    (net (code "153") (name "/USB_DN") (class "Default")
      (node (ref "IC6") (pin "25") (pinfunction "GPIO19_25") (pintype "passive"))
      (node (ref "USB1") (pin "5") (pinfunction "DN2_5") (pintype "passive"))
      (node (ref "USB1") (pin "7") (pinfunction "DN1_7") (pintype "passive"))
    )
    (net (code "154") (name "/USB_DP") (class "Default")
      (node (ref "IC6") (pin "26") (pinfunction "GPIO20_26") (pintype "passive"))
      (node (ref "USB1") (pin "6") (pinfunction "DP1_6") (pintype "passive"))
      (node (ref "USB1") (pin "8") (pinfunction "DP2_8") (pintype "passive"))
    )
    (net (code "155") (name "/USB_SIG_PTE9") (class "Default")
      (node (ref "IC1") (pin "36") (pinfunction "PTE9_36") (pintype "passive"))
      (node (ref "R3") (pin "2") (pinfunction "2_2") (pintype "passive"))
      (node (ref "R4") (pin "1") (pinfunction "1_1") (pintype "passive"))
    )
    (net (code "156") (name "/VRC_CTRL") (class "Default")
      (node (ref "IC1") (pin "11") (pinfunction "PTE13_11") (pintype "passive"))
      (node (ref "Q2") (pin "1") (pinfunction "B_1") (pintype "passive"))
      (node (ref "R27") (pin "1") (pinfunction "1_1") (pintype "passive"))
    )
    (net (code "157") (name "/WDI_TLF35584_PTD7") (class "Default")
      (node (ref "IC1") (pin "51") (pinfunction "PTD7_51") (pintype "passive"))
      (node (ref "R17") (pin "1") (pinfunction "1_1") (pintype "passive"))
    )
    (net (code "158") (name "/WS2812_CTRL") (class "Default")
      (node (ref "IC6") (pin "36") (pinfunction "SPICLK_N_36") (pintype "passive"))
      (node (ref "LED6") (pin "3") (pinfunction "DI_3") (pintype "passive"))
    )
    (net (code "159") (name "/XTAL") (class "Default")
      (node (ref "IC1") (pin "25") (pinfunction "XTAL_25") (pintype "passive"))
      (node (ref "R11") (pin "1") (pinfunction "1_1") (pintype "passive"))
    )
    (net (code "160") (name "/XTAL_N") (class "Default")
      (node (ref "C47") (pin "2") (pinfunction "2_2") (pintype "passive"))
      (node (ref "IC6") (pin "53") (pinfunction "XTAL_N_53") (pintype "passive"))
      (node (ref "Y2") (pin "3") (pinfunction "OSC2_3") (pintype "passive"))
    )
    (net (code "161") (name "/XTAL_P") (class "Default")
      (node (ref "IC6") (pin "54") (pinfunction "XTAL_P_54") (pintype "passive"))
      (node (ref "R33") (pin "1") (pinfunction "1_1") (pintype "passive"))
    )
    (net (code "162") (name "1.1V_CORE") (class "Default")
      (node (ref "C38") (pin "2") (pinfunction "2_2") (pintype "passive"))
      (node (ref "C39") (pin "2") (pinfunction "2_2") (pintype "passive"))
      (node (ref "C40") (pin "2") (pinfunction "2_2") (pintype "passive"))
      (node (ref "C41") (pin "2") (pinfunction "2_2") (pintype "passive"))
      (node (ref "C42") (pin "2") (pinfunction "2_2") (pintype "passive"))
      (node (ref "IC1") (pin "106") (pinfunction "V11_3_106") (pintype "passive"))
      (node (ref "IC1") (pin "149") (pinfunction "V11_4_149") (pintype "passive"))
      (node (ref "IC1") (pin "21") (pinfunction "V11_1_21") (pintype "passive"))
      (node (ref "IC1") (pin "59") (pinfunction "V11_2_59") (pintype "passive"))
    )
    (net (code "163") (name "1.5V_LOGIC") (class "Default")
      (node (ref "C18") (pin "2") (pinfunction "2_2") (pintype "passive"))
      (node (ref "C33") (pin "2") (pinfunction "2_2") (pintype "passive"))
      (node (ref "C34") (pin "2") (pinfunction "2_2") (pintype "passive"))
      (node (ref "C35") (pin "2") (pinfunction "2_2") (pintype "passive"))
      (node (ref "C36") (pin "2") (pinfunction "2_2") (pintype "passive"))
      (node (ref "C37") (pin "2") (pinfunction "2_2") (pintype "passive"))
      (node (ref "IC1") (pin "105") (pinfunction "V15_3_105") (pintype "passive"))
      (node (ref "IC1") (pin "148") (pinfunction "V15_4_148") (pintype "passive"))
      (node (ref "IC1") (pin "20") (pinfunction "V15_1_20") (pintype "passive"))
      (node (ref "IC1") (pin "60") (pinfunction "V15_2_60") (pintype "passive"))
      (node (ref "Q2") (pin "3") (pinfunction "E_3") (pintype "passive"))
      (node (ref "R27") (pin "2") (pinfunction "2_2") (pintype "passive"))
    )
    (net (code "164") (name "2.5V_FLASH") (class "Default")
      (node (ref "C30") (pin "2") (pinfunction "2_2") (pintype "passive"))
      (node (ref "C31") (pin "2") (pinfunction "2_2") (pintype "passive"))
      (node (ref "C32") (pin "2") (pinfunction "2_2") (pintype "passive"))
      (node (ref "IC1") (pin "19") (pinfunction "V25_19") (pintype "passive"))
    )
    (net (code "165") (name "3.3V_MCU") (class "Default")
      (node (ref "BTB1") (pin "30") (pinfunction "30_30") (pintype "passive"))
      (node (ref "C13") (pin "2") (pinfunction "2_2") (pintype "passive"))
      (node (ref "C14") (pin "2") (pinfunction "2_2") (pintype "passive"))
      (node (ref "C20") (pin "2") (pinfunction "2_2") (pintype "passive"))
      (node (ref "C21") (pin "2") (pinfunction "2_2") (pintype "passive"))
      (node (ref "C22") (pin "2") (pinfunction "2_2") (pintype "passive"))
      (node (ref "C23") (pin "2") (pinfunction "2_2") (pintype "passive"))
      (node (ref "C24") (pin "2") (pinfunction "2_2") (pintype "passive"))
      (node (ref "C25") (pin "2") (pinfunction "2_2") (pintype "passive"))
      (node (ref "C26") (pin "2") (pinfunction "2_2") (pintype "passive"))
      (node (ref "C27") (pin "2") (pinfunction "2_2") (pintype "passive"))
      (node (ref "C28") (pin "2") (pinfunction "2_2") (pintype "passive"))
      (node (ref "C29") (pin "2") (pinfunction "2_2") (pintype "passive"))
      (node (ref "C43") (pin "2") (pinfunction "2_2") (pintype "passive"))
      (node (ref "C44") (pin "1") (pinfunction "1_1") (pintype "passive"))
      (node (ref "C45") (pin "1") (pinfunction "1_1") (pintype "passive"))
      (node (ref "C48") (pin "2") (pinfunction "2_2") (pintype "passive"))
      (node (ref "C50") (pin "2") (pinfunction "2_2") (pintype "passive"))
      (node (ref "C51") (pin "2") (pinfunction "2_2") (pintype "passive"))
      (node (ref "C52") (pin "2") (pinfunction "2_2") (pintype "passive"))
      (node (ref "C54") (pin "2") (pinfunction "2_2") (pintype "passive"))
      (node (ref "IC1") (pin "108") (pinfunction "VDD_HV_A_2_108") (pintype "passive"))
      (node (ref "IC1") (pin "128") (pinfunction "VDD_HV_A_3_128") (pintype "passive"))
      (node (ref "IC1") (pin "151") (pinfunction "VDD_HV_A_4_151") (pintype "passive"))
      (node (ref "IC1") (pin "169") (pinfunction "VDD_HV_A_5_169") (pintype "passive"))
      (node (ref "IC1") (pin "18") (pinfunction "VDD_HV_A_1_18") (pintype "passive"))
      (node (ref "IC1") (pin "38") (pinfunction "VDD_HV_B_1_38") (pintype "passive"))
      (node (ref "IC1") (pin "57") (pinfunction "VDD_HV_B_2_57") (pintype "passive"))
      (node (ref "IC1") (pin "77") (pinfunction "VDD_HV_B_3_77") (pintype "passive"))
      (node (ref "IC2") (pin "30") (pinfunction "QUC_30") (pintype "passive"))
      (node (ref "IC3") (pin "5") (pinfunction "VIO_5") (pintype "passive"))
      (node (ref "IC4") (pin "8") (pinfunction "VCC_8") (pintype "passive"))
      (node (ref "IC5") (pin "5") (pinfunction "VCC_5") (pintype "passive"))
      (node (ref "IC6") (pin "20") (pinfunction "VDD3P3_RTC_20") (pintype "passive"))
      (node (ref "IC6") (pin "46") (pinfunction "VDD3P3_CPU_46") (pintype "passive"))
      (node (ref "IC6") (pin "55") (pinfunction "VDDA_1_55") (pintype "passive"))
      (node (ref "IC6") (pin "56") (pinfunction "VDDA_2_56") (pintype "passive"))
      (node (ref "J1") (pin "3") (pinfunction "3_3") (pintype "passive"))
      (node (ref "L3") (pin "1") (pinfunction "1_1") (pintype "passive"))
      (node (ref "R10") (pin "1") (pinfunction "1_1") (pintype "passive"))
      (node (ref "R18") (pin "1") (pinfunction "1_1") (pintype "passive"))
      (node (ref "R21") (pin "2") (pinfunction "2_2") (pintype "passive"))
      (node (ref "R22") (pin "2") (pinfunction "2_2") (pintype "passive"))
      (node (ref "R23") (pin "2") (pinfunction "2_2") (pintype "passive"))
      (node (ref "R24") (pin "2") (pinfunction "2_2") (pintype "passive"))
      (node (ref "R25") (pin "2") (pinfunction "2_2") (pintype "passive"))
      (node (ref "R26") (pin "2") (pinfunction "2_2") (pintype "passive"))
      (node (ref "R29") (pin "2") (pinfunction "2_2") (pintype "passive"))
      (node (ref "R30") (pin "2") (pinfunction "2_2") (pintype "passive"))
      (node (ref "R5") (pin "2") (pinfunction "2_2") (pintype "passive"))
      (node (ref "R9") (pin "1") (pinfunction "1_1") (pintype "passive"))
      (node (ref "S1") (pin "5") (pinfunction "VCC_5") (pintype "passive"))
    )
    (net (code "166") (name "5V_COM") (class "Default")
      (node (ref "BTB1") (pin "31") (pinfunction "31_31") (pintype "passive"))
      (node (ref "C10") (pin "1") (pinfunction "1_1") (pintype "passive"))
      (node (ref "C11") (pin "1") (pinfunction "1_1") (pintype "passive"))
      (node (ref "C17") (pin "1") (pinfunction "1_1") (pintype "passive"))
      (node (ref "C19") (pin "1") (pinfunction "1_1") (pintype "passive"))
      (node (ref "IC2") (pin "31") (pinfunction "QCO_31") (pintype "passive"))
      (node (ref "IC3") (pin "3") (pinfunction "VCC_3") (pintype "passive"))
      (node (ref "LED6") (pin "4") (pinfunction "VDD_4") (pintype "passive"))
      (node (ref "Q2") (pin "2") (pinfunction "C_2") (pintype "passive"))
      (node (ref "Q2") (pin "4") (pinfunction "C_4") (pintype "passive"))
      (node (ref "R28") (pin "2") (pinfunction "2_2") (pintype "passive"))
    )
    (net (code "167") (name "5V_IN") (class "Default")
      (node (ref "D2") (pin "2") (pinfunction "A_2") (pintype "passive"))
      (node (ref "F2") (pin "2") (pinfunction "2_2") (pintype "passive"))
      (node (ref "R3") (pin "1") (pinfunction "1_1") (pintype "passive"))
    )
    (net (code "168") (name "6V_BUCK") (class "Default")
      (node (ref "C1") (pin "1") (pinfunction "+_1") (pintype "passive"))
      (node (ref "C2") (pin "2") (pinfunction "2_2") (pintype "passive"))
      (node (ref "C3") (pin "2") (pinfunction "2_2") (pintype "passive"))
      (node (ref "L1") (pin "2") (pinfunction "2_2") (pintype "passive"))
      (node (ref "R6") (pin "2") (pinfunction "2_2") (pintype "passive"))
    )
    (net (code "169") (name "GLVMS-") (class "Default")
      (node (ref "BTB2") (pin "29") (pinfunction "29_29") (pintype "passive"))
      (node (ref "BTB2") (pin "30") (pinfunction "30_30") (pintype "passive"))
      (node (ref "F1") (pin "2") (pinfunction "2_2") (pintype "passive"))
    )
    (net (code "170") (name "GND") (class "Default")
      (node (ref "BTB1") (pin "60") (pinfunction "60_60") (pintype "passive"))
      (node (ref "BTB2") (pin "31") (pinfunction "31_31") (pintype "passive"))
      (node (ref "BTB2") (pin "32") (pinfunction "32_32") (pintype "passive"))
      (node (ref "C1") (pin "2") (pinfunction "-_2") (pintype "passive"))
      (node (ref "C10") (pin "2") (pinfunction "2_2") (pintype "passive"))
      (node (ref "C11") (pin "2") (pinfunction "2_2") (pintype "passive"))
      (node (ref "C12") (pin "1") (pinfunction "1_1") (pintype "passive"))
      (node (ref "C13") (pin "1") (pinfunction "1_1") (pintype "passive"))
      (node (ref "C14") (pin "1") (pinfunction "1_1") (pintype "passive"))
      (node (ref "C15") (pin "2") (pinfunction "2_2") (pintype "passive"))
      (node (ref "C16") (pin "1") (pinfunction "1_1") (pintype "passive"))
      (node (ref "C17") (pin "2") (pinfunction "2_2") (pintype "passive"))
      (node (ref "C18") (pin "1") (pinfunction "1_1") (pintype "passive"))
      (node (ref "C19") (pin "2") (pinfunction "2_2") (pintype "passive"))
      (node (ref "C2") (pin "1") (pinfunction "1_1") (pintype "passive"))
      (node (ref "C20") (pin "1") (pinfunction "1_1") (pintype "passive"))
      (node (ref "C21") (pin "1") (pinfunction "1_1") (pintype "passive"))
      (node (ref "C22") (pin "1") (pinfunction "1_1") (pintype "passive"))
      (node (ref "C23") (pin "1") (pinfunction "1_1") (pintype "passive"))
      (node (ref "C24") (pin "1") (pinfunction "1_1") (pintype "passive"))
      (node (ref "C25") (pin "1") (pinfunction "1_1") (pintype "passive"))
      (node (ref "C26") (pin "1") (pinfunction "1_1") (pintype "passive"))
      (node (ref "C27") (pin "1") (pinfunction "1_1") (pintype "passive"))
      (node (ref "C28") (pin "1") (pinfunction "1_1") (pintype "passive"))
      (node (ref "C29") (pin "1") (pinfunction "1_1") (pintype "passive"))
      (node (ref "C3") (pin "1") (pinfunction "1_1") (pintype "passive"))
      (node (ref "C30") (pin "1") (pinfunction "1_1") (pintype "passive"))
      (node (ref "C31") (pin "1") (pinfunction "1_1") (pintype "passive"))
      (node (ref "C32") (pin "1") (pinfunction "1_1") (pintype "passive"))
      (node (ref "C33") (pin "1") (pinfunction "1_1") (pintype "passive"))
      (node (ref "C34") (pin "1") (pinfunction "1_1") (pintype "passive"))
      (node (ref "C35") (pin "1") (pinfunction "1_1") (pintype "passive"))
      (node (ref "C36") (pin "1") (pinfunction "1_1") (pintype "passive"))
      (node (ref "C37") (pin "1") (pinfunction "1_1") (pintype "passive"))
      (node (ref "C38") (pin "1") (pinfunction "1_1") (pintype "passive"))
      (node (ref "C39") (pin "1") (pinfunction "1_1") (pintype "passive"))
      (node (ref "C4") (pin "1") (pinfunction "1_1") (pintype "passive"))
      (node (ref "C40") (pin "1") (pinfunction "1_1") (pintype "passive"))
      (node (ref "C41") (pin "1") (pinfunction "1_1") (pintype "passive"))
      (node (ref "C42") (pin "1") (pinfunction "1_1") (pintype "passive"))
      (node (ref "C43") (pin "1") (pinfunction "1_1") (pintype "passive"))
      (node (ref "C44") (pin "2") (pinfunction "2_2") (pintype "passive"))
      (node (ref "C45") (pin "2") (pinfunction "2_2") (pintype "passive"))
      (node (ref "C46") (pin "2") (pinfunction "2_2") (pintype "passive"))
      (node (ref "C47") (pin "1") (pinfunction "1_1") (pintype "passive"))
      (node (ref "C48") (pin "1") (pinfunction "1_1") (pintype "passive"))
      (node (ref "C49") (pin "1") (pinfunction "1_1") (pintype "passive"))
      (node (ref "C5") (pin "2") (pinfunction "2_2") (pintype "passive"))
      (node (ref "C50") (pin "1") (pinfunction "1_1") (pintype "passive"))
      (node (ref "C51") (pin "1") (pinfunction "1_1") (pintype "passive"))
      (node (ref "C52") (pin "1") (pinfunction "1_1") (pintype "passive"))
      (node (ref "C53") (pin "1") (pinfunction "1_1") (pintype "passive"))
      (node (ref "C54") (pin "1") (pinfunction "1_1") (pintype "passive"))
      (node (ref "C6") (pin "2") (pinfunction "-_2") (pintype "passive"))
      (node (ref "C7") (pin "2") (pinfunction "-_2") (pintype "passive"))
      (node (ref "C8") (pin "1") (pinfunction "1_1") (pintype "passive"))
      (node (ref "C9") (pin "1") (pinfunction "1_1") (pintype "passive"))
      (node (ref "D4") (pin "1") (pinfunction "1_1") (pintype "passive"))
      (node (ref "IC1") (pin "107") (pinfunction "VSS_6_107") (pintype "passive"))
      (node (ref "IC1") (pin "127") (pinfunction "VSS_7_127") (pintype "passive"))
      (node (ref "IC1") (pin "150") (pinfunction "VSS_8_150") (pintype "passive"))
      (node (ref "IC1") (pin "168") (pinfunction "VSS_9_168") (pintype "passive"))
      (node (ref "IC1") (pin "17") (pinfunction "VREFL_17") (pintype "passive"))
      (node (ref "IC1") (pin "22") (pinfunction "VSS_1_22") (pintype "passive"))
      (node (ref "IC1") (pin "24") (pinfunction "VSS_2_24") (pintype "passive"))
      (node (ref "IC1") (pin "37") (pinfunction "VSS_3_37") (pintype "passive"))
      (node (ref "IC1") (pin "58") (pinfunction "VSS_4_58") (pintype "passive"))
      (node (ref "IC1") (pin "78") (pinfunction "VSS_5_78") (pintype "passive"))
      (node (ref "IC2") (pin "1") (pinfunction "BSG_1") (pintype "passive"))
      (node (ref "IC2") (pin "23") (pinfunction "SEC_23") (pintype "passive"))
      (node (ref "IC2") (pin "24") (pinfunction "FRE_24") (pintype "passive"))
      (node (ref "IC2") (pin "27") (pinfunction "GST_27") (pintype "passive"))
      (node (ref "IC2") (pin "28") (pinfunction "AG3_28") (pintype "passive"))
      (node (ref "IC2") (pin "3") (pinfunction "ENA_3") (pintype "passive"))
      (node (ref "IC2") (pin "39") (pinfunction "N.C._4_39") (pintype "passive"))
      (node (ref "IC2") (pin "4") (pinfunction "WAK_4") (pintype "passive"))
      (node (ref "IC2") (pin "40") (pinfunction "PG2_40") (pintype "passive"))
      (node (ref "IC2") (pin "41") (pinfunction "PG1_41") (pintype "passive"))
      (node (ref "IC2") (pin "48") (pinfunction "RSL_48") (pintype "passive"))
      (node (ref "IC2") (pin "49") (pinfunction "EP_49") (pintype "passive"))
      (node (ref "IC2") (pin "6") (pinfunction "AG1_6") (pintype "passive"))
      (node (ref "IC2") (pin "7") (pinfunction "AG2_7") (pintype "passive"))
      (node (ref "IC2") (pin "8") (pinfunction "AGS1_8") (pintype "passive"))
      (node (ref "IC2") (pin "9") (pinfunction "AGS2_9") (pintype "passive"))
      (node (ref "IC3") (pin "2") (pinfunction "GND_2") (pintype "passive"))
      (node (ref "IC4") (pin "1") (pinfunction "A0_1") (pintype "passive"))
      (node (ref "IC4") (pin "2") (pinfunction "A1_2") (pintype "passive"))
      (node (ref "IC4") (pin "3") (pinfunction "A2_3") (pintype "passive"))
      (node (ref "IC4") (pin "4") (pinfunction "GND_4") (pintype "passive"))
      (node (ref "IC5") (pin "2") (pinfunction "GND_2") (pintype "passive"))
      (node (ref "IC5") (pin "6") (pinfunction "~{OE}_6") (pintype "passive"))
      (node (ref "IC6") (pin "57") (pinfunction "EP_57") (pintype "passive"))
      (node (ref "J1") (pin "5") (pinfunction "5_5") (pintype "passive"))
      (node (ref "J3") (pin "1") (pinfunction "GND_1") (pintype "passive"))
      (node (ref "J3") (pin "3") (pinfunction "GND_3") (pintype "passive"))
      (node (ref "L4") (pin "1") (pinfunction "1_1") (pintype "passive"))
      (node (ref "LED4") (pin "1") (pinfunction "-_1") (pintype "passive"))
      (node (ref "LED5") (pin "1") (pinfunction "-_1") (pintype "passive"))
      (node (ref "LED6") (pin "2") (pinfunction "GND_2") (pintype "passive"))
      (node (ref "R14") (pin "2") (pinfunction "2_2") (pintype "passive"))
      (node (ref "R32") (pin "2") (pinfunction "2_2") (pintype "passive"))
      (node (ref "R34") (pin "1") (pinfunction "1_1") (pintype "passive"))
      (node (ref "R35") (pin "1") (pinfunction "1_1") (pintype "passive"))
      (node (ref "R36") (pin "2") (pinfunction "2_2") (pintype "passive"))
      (node (ref "R4") (pin "2") (pinfunction "2_2") (pintype "passive"))
      (node (ref "R7") (pin "1") (pinfunction "1_1") (pintype "passive"))
      (node (ref "R8") (pin "1") (pinfunction "1_1") (pintype "passive"))
      (node (ref "RT1") (pin "2") (pinfunction "2_2") (pintype "passive"))
      (node (ref "S1") (pin "2") (pinfunction "GND_2") (pintype "passive"))
      (node (ref "SW1") (pin "1") (pinfunction "COMMON_1") (pintype "passive"))
      (node (ref "SW4") (pin "2") (pinfunction "NO_2") (pintype "passive"))
      (node (ref "SW5") (pin "2") (pinfunction "NO_2") (pintype "passive"))
      (node (ref "USB1") (pin "1") (pinfunction "GND_1") (pintype "passive"))
      (node (ref "USB1") (pin "12") (pinfunction "GND_12") (pintype "passive"))
      (node (ref "USB1") (pin "13") (pinfunction "SHELL_13") (pintype "passive"))
      (node (ref "USB1") (pin "14") (pinfunction "SHELL_14") (pintype "passive"))
      (node (ref "Y1") (pin "2") (pinfunction "GND_2") (pintype "passive"))
      (node (ref "Y1") (pin "4") (pinfunction "GND_4") (pintype "passive"))
      (node (ref "Y2") (pin "2") (pinfunction "GND_2") (pintype "passive"))
      (node (ref "Y2") (pin "4") (pinfunction "GND_4") (pintype "passive"))
    )
    (net (code "171") (name "Net-(C6-+)") (class "Default")
      (node (ref "C6") (pin "1") (pinfunction "+_1") (pintype "passive"))
      (node (ref "C9") (pin "2") (pinfunction "2_2") (pintype "passive"))
      (node (ref "D3") (pin "1") (pinfunction "K_1") (pintype "passive"))
      (node (ref "IC2") (pin "2") (pinfunction "VST_2") (pintype "passive"))
      (node (ref "IC2") (pin "44") (pinfunction "N.C._6_44") (pintype "passive"))
      (node (ref "IC2") (pin "45") (pinfunction "VS1_45") (pintype "passive"))
    )
    (net (code "172") (name "Net-(C7-+)") (class "Default")
      (node (ref "C7") (pin "1") (pinfunction "+_1") (pintype "passive"))
      (node (ref "C8") (pin "2") (pinfunction "2_2") (pintype "passive"))
      (node (ref "D1") (pin "1") (pinfunction "K_1") (pintype "passive"))
      (node (ref "D2") (pin "1") (pinfunction "K_1") (pintype "passive"))
      (node (ref "L2") (pin "1") (pinfunction "1_1") (pintype "passive"))
    )
    (net (code "173") (name "Net-(D1-A)") (class "Default")
      (node (ref "D1") (pin "2") (pinfunction "A_2") (pintype "passive"))
      (node (ref "F1") (pin "1") (pinfunction "1_1") (pintype "passive"))
    )
    (net (code "174") (name "Net-(D3-A)") (class "Default")
      (node (ref "D3") (pin "2") (pinfunction "A_2") (pintype "passive"))
      (node (ref "D4") (pin "2") (pinfunction "2_2") (pintype "passive"))
      (node (ref "L2") (pin "2") (pinfunction "2_2") (pintype "passive"))
      (node (ref "Q1") (pin "5") (pinfunction "D_5") (pintype "passive"))
      (node (ref "Q1") (pin "6") (pinfunction "D_6") (pintype "passive"))
      (node (ref "Q1") (pin "7") (pinfunction "D_7") (pintype "passive"))
      (node (ref "Q1") (pin "8") (pinfunction "D_8") (pintype "passive"))
    )
    (net (code "175") (name "Net-(IC1-VREFH)") (class "Default")
      (node (ref "C5") (pin "1") (pinfunction "1_1") (pintype "passive"))
      (node (ref "IC1") (pin "16") (pinfunction "VREFH_16") (pintype "passive"))
      (node (ref "R9") (pin "2") (pinfunction "2_2") (pintype "passive"))
    )
    (net (code "176") (name "Net-(IC2-DRG)") (class "Default")
      (node (ref "IC2") (pin "46") (pinfunction "DRG_46") (pintype "passive"))
      (node (ref "Q1") (pin "4") (pinfunction "G_4") (pintype "passive"))
    )
    (net (code "177") (name "Net-(IC2-FB1)") (class "Default")
      (node (ref "IC2") (pin "34") (pinfunction "N.C._1_34") (pintype "passive"))
      (node (ref "IC2") (pin "35") (pinfunction "N.C._2_35") (pintype "passive"))
      (node (ref "IC2") (pin "36") (pinfunction "N.C._3_36") (pintype "passive"))
      (node (ref "IC2") (pin "37") (pinfunction "FB1_37") (pintype "passive"))
      (node (ref "IC2") (pin "38") (pinfunction "FB2_38") (pintype "passive"))
      (node (ref "R6") (pin "1") (pinfunction "1_1") (pintype "passive"))
    )
    (net (code "178") (name "Net-(IC2-INT)") (class "Default")
      (node (ref "IC2") (pin "18") (pinfunction "INT_18") (pintype "passive"))
      (node (ref "R20") (pin "2") (pinfunction "2_2") (pintype "passive"))
    )
    (net (code "179") (name "Net-(IC2-N.C._5)") (class "Default")
      (node (ref "IC2") (pin "42") (pinfunction "SW1_42") (pintype "passive"))
      (node (ref "IC2") (pin "43") (pinfunction "N.C._5_43") (pintype "passive"))
      (node (ref "L1") (pin "1") (pinfunction "1_1") (pintype "passive"))
    )
    (net (code "180") (name "Net-(IC2-QST)") (class "Default")
      (node (ref "C12") (pin "2") (pinfunction "2_2") (pintype "passive"))
      (node (ref "IC2") (pin "5") (pinfunction "QST_5") (pintype "passive"))
    )
    (net (code "181") (name "Net-(IC2-ROT)") (class "Default")
      (node (ref "IC2") (pin "17") (pinfunction "ROT_17") (pintype "passive"))
      (node (ref "R19") (pin "2") (pinfunction "2_2") (pintype "passive"))
    )
    (net (code "182") (name "Net-(IC2-RSH)") (class "Default")
      (node (ref "IC2") (pin "47") (pinfunction "RSH_47") (pintype "passive"))
      (node (ref "Q1") (pin "1") (pinfunction "S_1") (pintype "passive"))
      (node (ref "Q1") (pin "2") (pinfunction "S_2") (pintype "passive"))
      (node (ref "Q1") (pin "3") (pinfunction "S_3") (pintype "passive"))
      (node (ref "R8") (pin "2") (pinfunction "2_2") (pintype "passive"))
    )
    (net (code "183") (name "Net-(IC2-SCL)") (class "Default")
      (node (ref "IC2") (pin "14") (pinfunction "SCL_14") (pintype "passive"))
      (node (ref "R15") (pin "2") (pinfunction "2_2") (pintype "passive"))
    )
    (net (code "184") (name "Net-(IC2-SCS)") (class "Default")
      (node (ref "IC2") (pin "15") (pinfunction "SCS_15") (pintype "passive"))
      (node (ref "R16") (pin "2") (pinfunction "2_2") (pintype "passive"))
    )
    (net (code "185") (name "Net-(IC2-SDI)") (class "Default")
      (node (ref "IC2") (pin "12") (pinfunction "SDI_12") (pintype "passive"))
      (node (ref "R12") (pin "2") (pinfunction "2_2") (pintype "passive"))
    )
    (net (code "186") (name "Net-(IC2-SDO)") (class "Default")
      (node (ref "IC2") (pin "13") (pinfunction "SDO_13") (pintype "passive"))
      (node (ref "R13") (pin "2") (pinfunction "2_2") (pintype "passive"))
    )
    (net (code "187") (name "Net-(IC2-STU)") (class "Default")
      (node (ref "IC2") (pin "25") (pinfunction "STU_25") (pintype "passive"))
      (node (ref "R14") (pin "1") (pinfunction "1_1") (pintype "passive"))
    )
    (net (code "188") (name "Net-(IC2-WDI)") (class "Default")
      (node (ref "IC2") (pin "16") (pinfunction "WDI_16") (pintype "passive"))
      (node (ref "R17") (pin "2") (pinfunction "2_2") (pintype "passive"))
    )
    (net (code "189") (name "Net-(J3-SIG)") (class "Default")
      (node (ref "J3") (pin "2") (pinfunction "SIG_2") (pintype "passive"))
      (node (ref "R38") (pin "1") (pinfunction "1_1") (pintype "passive"))
      (node (ref "R40") (pin "2") (pinfunction "2_2") (pintype "passive"))
    )
    (net (code "190") (name "Net-(L4-Pad2)") (class "Default")
      (node (ref "L4") (pin "2") (pinfunction "2_2") (pintype "passive"))
      (node (ref "R39") (pin "2") (pinfunction "2_2") (pintype "passive"))
      (node (ref "R40") (pin "1") (pinfunction "1_1") (pintype "passive"))
    )
    (net (code "191") (name "Net-(LED1-A)") (class "Default")
      (node (ref "LED1") (pin "2") (pinfunction "A_2") (pintype "passive"))
      (node (ref "R21") (pin "1") (pinfunction "1_1") (pintype "passive"))
    )
    (net (code "192") (name "Net-(LED2-A)") (class "Default")
      (node (ref "LED2") (pin "2") (pinfunction "A_2") (pintype "passive"))
      (node (ref "R23") (pin "1") (pinfunction "1_1") (pintype "passive"))
    )
    (net (code "193") (name "Net-(LED3-+)") (class "Default")
      (node (ref "LED3") (pin "2") (pinfunction "+_2") (pintype "passive"))
      (node (ref "R25") (pin "1") (pinfunction "1_1") (pintype "passive"))
    )
    (net (code "194") (name "Net-(LED4-+)") (class "Default")
      (node (ref "LED4") (pin "2") (pinfunction "+_2") (pintype "passive"))
      (node (ref "R26") (pin "1") (pinfunction "1_1") (pintype "passive"))
    )
    (net (code "195") (name "Net-(LED5-+)") (class "Default")
      (node (ref "LED5") (pin "2") (pinfunction "+_2") (pintype "passive"))
      (node (ref "R28") (pin "1") (pinfunction "1_1") (pintype "passive"))
    )
    (net (code "196") (name "Net-(R38-Pad2)") (class "Default")
      (node (ref "R38") (pin "2") (pinfunction "2_2") (pintype "passive"))
      (node (ref "RF1") (pin "1") (pinfunction "1_1") (pintype "passive"))
    )
    (net (code "197") (name "Net-(SW2-NO)") (class "Default")
      (node (ref "R22") (pin "1") (pinfunction "1_1") (pintype "passive"))
      (node (ref "SW2") (pin "2") (pinfunction "NO_2") (pintype "passive"))
    )
    (net (code "198") (name "Net-(SW3-NO)") (class "Default")
      (node (ref "R24") (pin "1") (pinfunction "1_1") (pintype "passive"))
      (node (ref "SW3") (pin "2") (pinfunction "NO_2") (pintype "passive"))
    )
    (net (code "199") (name "Net-(Y1-OSC1)") (class "Default")
      (node (ref "C15") (pin "1") (pinfunction "1_1") (pintype "passive"))
      (node (ref "R11") (pin "2") (pinfunction "2_2") (pintype "passive"))
      (node (ref "Y1") (pin "1") (pinfunction "OSC1_1") (pintype "passive"))
    )
    (net (code "200") (name "Net-(Y2-OSC1)") (class "Default")
      (node (ref "C46") (pin "1") (pinfunction "1_1") (pintype "passive"))
      (node (ref "R33") (pin "2") (pinfunction "2_2") (pintype "passive"))
      (node (ref "Y2") (pin "1") (pinfunction "OSC1_1") (pintype "passive"))
    )
    (net (code "201") (name "VBUS") (class "Default")
      (node (ref "F2") (pin "1") (pinfunction "1_1") (pintype "passive"))
      (node (ref "J1") (pin "1") (pinfunction "1_1") (pintype "passive"))
      (node (ref "USB1") (pin "11") (pinfunction "VBUS_11") (pintype "passive"))
      (node (ref "USB1") (pin "2") (pinfunction "VBUS_2") (pintype "passive"))
    )
    (net (code "202") (name "VDD_3P3") (class "Default")
      (node (ref "C53") (pin "2") (pinfunction "2_2") (pintype "passive"))
      (node (ref "IC6") (pin "2") (pinfunction "VDD3P3_1_2") (pintype "passive"))
      (node (ref "IC6") (pin "3") (pinfunction "VDD3P3_2_3") (pintype "passive"))
      (node (ref "L3") (pin "2") (pinfunction "2_2") (pintype "passive"))
    )
    (net (code "203") (name "VDD_SPI") (class "Default")
      (node (ref "C49") (pin "2") (pinfunction "2_2") (pintype "passive"))
      (node (ref "IC6") (pin "29") (pinfunction "VDD_SPI_29") (pintype "passive"))
    )
    (net (code "204") (name "unconnected-(BTB1-Pad32)") (class "Default")
      (node (ref "BTB1") (pin "32") (pinfunction "32_32") (pintype "passive"))
    )
    (net (code "205") (name "unconnected-(BTB2-Pad28)") (class "Default")
      (node (ref "BTB2") (pin "28") (pinfunction "28_28") (pintype "passive"))
    )
    (net (code "206") (name "unconnected-(IC2-ERR-Pad20)") (class "Default")
      (node (ref "IC2") (pin "20") (pinfunction "ERR_20") (pintype "passive+no_connect"))
    )
    (net (code "207") (name "unconnected-(IC2-EVC-Pad21)") (class "Default")
      (node (ref "IC2") (pin "21") (pinfunction "EVC_21") (pintype "passive+no_connect"))
    )
    (net (code "208") (name "unconnected-(IC2-QT1-Pad33)") (class "Default")
      (node (ref "IC2") (pin "33") (pinfunction "QT1_33") (pintype "passive+no_connect"))
    )
    (net (code "209") (name "unconnected-(IC2-QT2-Pad32)") (class "Default")
      (node (ref "IC2") (pin "32") (pinfunction "QT2_32") (pintype "passive+no_connect"))
    )
    (net (code "210") (name "unconnected-(IC2-QVR-Pad29)") (class "Default")
      (node (ref "IC2") (pin "29") (pinfunction "QVR_29") (pintype "passive+no_connect"))
    )
    (net (code "211") (name "unconnected-(IC2-SS1-Pad11)") (class "Default")
      (node (ref "IC2") (pin "11") (pinfunction "SS1_11") (pintype "passive+no_connect"))
    )
    (net (code "212") (name "unconnected-(IC2-SS2-Pad10)") (class "Default")
      (node (ref "IC2") (pin "10") (pinfunction "SS2_10") (pintype "passive+no_connect"))
    )
    (net (code "213") (name "unconnected-(IC2-SYN-Pad19)") (class "Default")
      (node (ref "IC2") (pin "19") (pinfunction "SYN_19") (pintype "passive+no_connect"))
    )
    (net (code "214") (name "unconnected-(IC2-VCI-Pad26)") (class "Default")
      (node (ref "IC2") (pin "26") (pinfunction "VCI_26") (pintype "passive+no_connect"))
    )
    (net (code "215") (name "unconnected-(IC6-GPIO1-Pad6)") (class "Default")
      (node (ref "IC6") (pin "6") (pinfunction "GPIO1_6") (pintype "passive"))
    )
    (net (code "216") (name "unconnected-(IC6-GPIO2-Pad7)") (class "Default")
      (node (ref "IC6") (pin "7") (pinfunction "GPIO2_7") (pintype "passive"))
    )
    (net (code "217") (name "unconnected-(IC6-GPIO3-Pad8)") (class "Default")
      (node (ref "IC6") (pin "8") (pinfunction "GPIO3_8") (pintype "passive+no_connect"))
    )
    (net (code "218") (name "unconnected-(IC6-GPIO4-Pad9)") (class "Default")
      (node (ref "IC6") (pin "9") (pinfunction "GPIO4_9") (pintype "passive"))
    )
    (net (code "219") (name "unconnected-(IC6-GPIO5-Pad10)") (class "Default")
      (node (ref "IC6") (pin "10") (pinfunction "GPIO5_10") (pintype "passive"))
    )
    (net (code "220") (name "unconnected-(IC6-GPIO6-Pad11)") (class "Default")
      (node (ref "IC6") (pin "11") (pinfunction "GPIO6_11") (pintype "passive"))
    )
    (net (code "221") (name "unconnected-(IC6-GPIO7-Pad12)") (class "Default")
      (node (ref "IC6") (pin "12") (pinfunction "GPIO7_12") (pintype "passive"))
    )
    (net (code "222") (name "unconnected-(IC6-GPIO8-Pad13)") (class "Default")
      (node (ref "IC6") (pin "13") (pinfunction "GPIO8_13") (pintype "passive"))
    )
    (net (code "223") (name "unconnected-(IC6-GPIO9-Pad14)") (class "Default")
      (node (ref "IC6") (pin "14") (pinfunction "GPIO9_14") (pintype "passive"))
    )
    (net (code "224") (name "unconnected-(IC6-GPIO10-Pad15)") (class "Default")
      (node (ref "IC6") (pin "15") (pinfunction "GPIO10_15") (pintype "passive"))
    )
    (net (code "225") (name "unconnected-(IC6-GPIO11-Pad16)") (class "Default")
      (node (ref "IC6") (pin "16") (pinfunction "GPIO11_16") (pintype "passive"))
    )
    (net (code "226") (name "unconnected-(IC6-GPIO12-Pad17)") (class "Default")
      (node (ref "IC6") (pin "17") (pinfunction "GPIO12_17") (pintype "passive"))
    )
    (net (code "227") (name "unconnected-(IC6-GPIO13-Pad18)") (class "Default")
      (node (ref "IC6") (pin "18") (pinfunction "GPIO13_18") (pintype "passive"))
    )
    (net (code "228") (name "unconnected-(IC6-GPIO14-Pad19)") (class "Default")
      (node (ref "IC6") (pin "19") (pinfunction "GPIO14_19") (pintype "passive"))
    )
    (net (code "229") (name "unconnected-(IC6-GPIO17-Pad23)") (class "Default")
      (node (ref "IC6") (pin "23") (pinfunction "GPIO17_23") (pintype "passive"))
    )
    (net (code "230") (name "unconnected-(IC6-GPIO18-Pad24)") (class "Default")
      (node (ref "IC6") (pin "24") (pinfunction "GPIO18_24") (pintype "passive"))
    )
    (net (code "231") (name "unconnected-(IC6-GPIO33-Pad38)") (class "Default")
      (node (ref "IC6") (pin "38") (pinfunction "GPIO33_38") (pintype "passive"))
    )
    (net (code "232") (name "unconnected-(IC6-GPIO34-Pad39)") (class "Default")
      (node (ref "IC6") (pin "39") (pinfunction "GPIO34_39") (pintype "passive"))
    )
    (net (code "233") (name "unconnected-(IC6-GPIO45-Pad51)") (class "Default")
      (node (ref "IC6") (pin "51") (pinfunction "GPIO45_51") (pintype "passive+no_connect"))
    )
    (net (code "234") (name "unconnected-(IC6-GPIO46-Pad52)") (class "Default")
      (node (ref "IC6") (pin "52") (pinfunction "GPIO46_52") (pintype "passive+no_connect"))
    )
    (net (code "235") (name "unconnected-(IC6-SPICLK-Pad33)") (class "Default")
      (node (ref "IC6") (pin "33") (pinfunction "SPICLK_33") (pintype "passive"))
    )
    (net (code "236") (name "unconnected-(IC6-SPICS0-Pad32)") (class "Default")
      (node (ref "IC6") (pin "32") (pinfunction "SPICS0_32") (pintype "passive"))
    )
    (net (code "237") (name "unconnected-(IC6-SPICS1-Pad28)") (class "Default")
      (node (ref "IC6") (pin "28") (pinfunction "SPICS1_28") (pintype "passive"))
    )
    (net (code "238") (name "unconnected-(IC6-SPID-Pad35)") (class "Default")
      (node (ref "IC6") (pin "35") (pinfunction "SPID_35") (pintype "passive"))
    )
    (net (code "239") (name "unconnected-(IC6-SPIHD-Pad30)") (class "Default")
      (node (ref "IC6") (pin "30") (pinfunction "SPIHD_30") (pintype "passive"))
    )
    (net (code "240") (name "unconnected-(IC6-SPIQ-Pad34)") (class "Default")
      (node (ref "IC6") (pin "34") (pinfunction "SPIQ_34") (pintype "passive"))
    )
    (net (code "241") (name "unconnected-(IC6-SPIWP-Pad31)") (class "Default")
      (node (ref "IC6") (pin "31") (pinfunction "SPIWP_31") (pintype "passive"))
    )
    (net (code "242") (name "unconnected-(IC6-U0RXD-Pad50)") (class "Default")
      (node (ref "IC6") (pin "50") (pinfunction "U0RXD_50") (pintype "passive"))
    )
    (net (code "243") (name "unconnected-(IC6-U0TXD-Pad49)") (class "Default")
      (node (ref "IC6") (pin "49") (pinfunction "U0TXD_49") (pintype "passive"))
    )
    (net (code "244") (name "unconnected-(IC6-XTAL_32K_N-Pad22)") (class "Default")
      (node (ref "IC6") (pin "22") (pinfunction "XTAL_32K_N_22") (pintype "passive"))
    )
    (net (code "245") (name "unconnected-(IC6-XTAL_32K_P-Pad21)") (class "Default")
      (node (ref "IC6") (pin "21") (pinfunction "XTAL_32K_P_21") (pintype "passive"))
    )
    (net (code "246") (name "unconnected-(LED6-DO-Pad1)") (class "Default")
      (node (ref "LED6") (pin "1") (pinfunction "DO_1") (pintype "passive+no_connect"))
    )
    (net (code "247") (name "unconnected-(RF1-Pad2)") (class "Default")
      (node (ref "RF1") (pin "2") (pinfunction "2_2") (pintype "passive"))
    )
    (net (code "248") (name "unconnected-(USB1-SBU1-Pad9)") (class "Default")
      (node (ref "USB1") (pin "9") (pinfunction "SBU1_9") (pintype "passive"))
    )
    (net (code "249") (name "unconnected-(USB1-SBU2-Pad3)") (class "Default")
      (node (ref "USB1") (pin "3") (pinfunction "SBU2_3") (pintype "passive"))
    )
  )
)
